# M225A.net
KiCad netlist of a schematic drawn in EAGLE
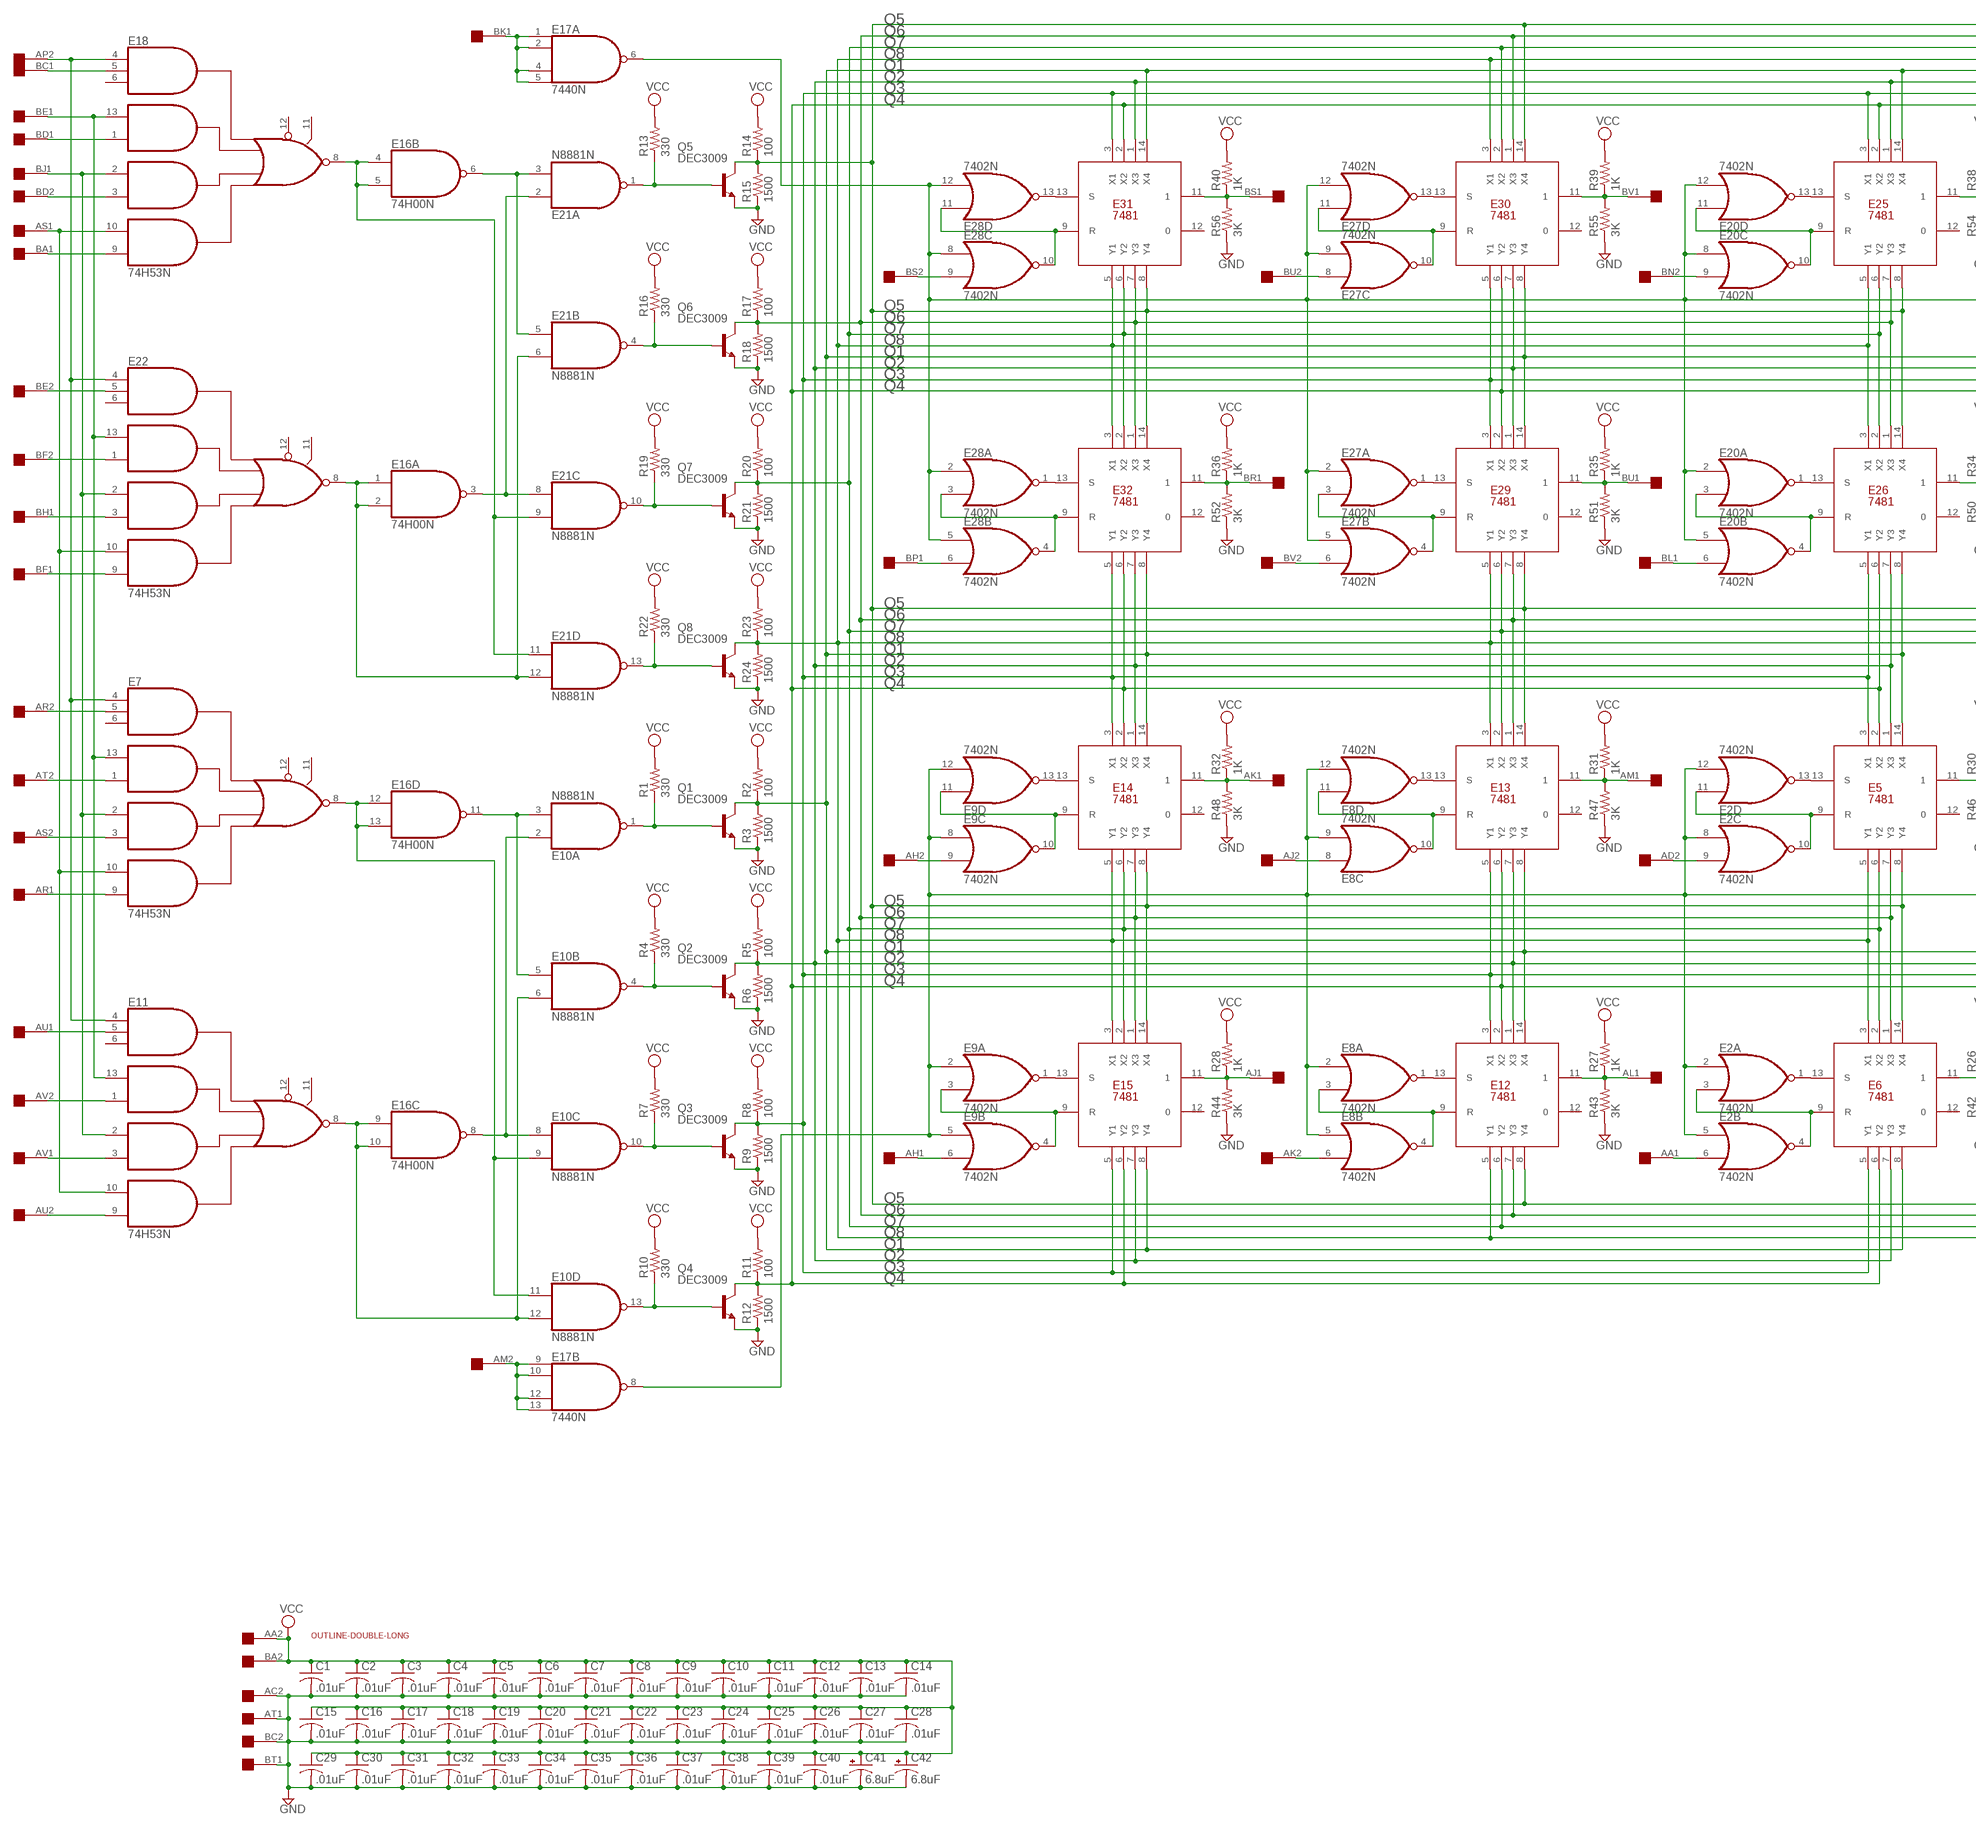
[diagram p0: schematic, sheet 1, part 1 of 2]
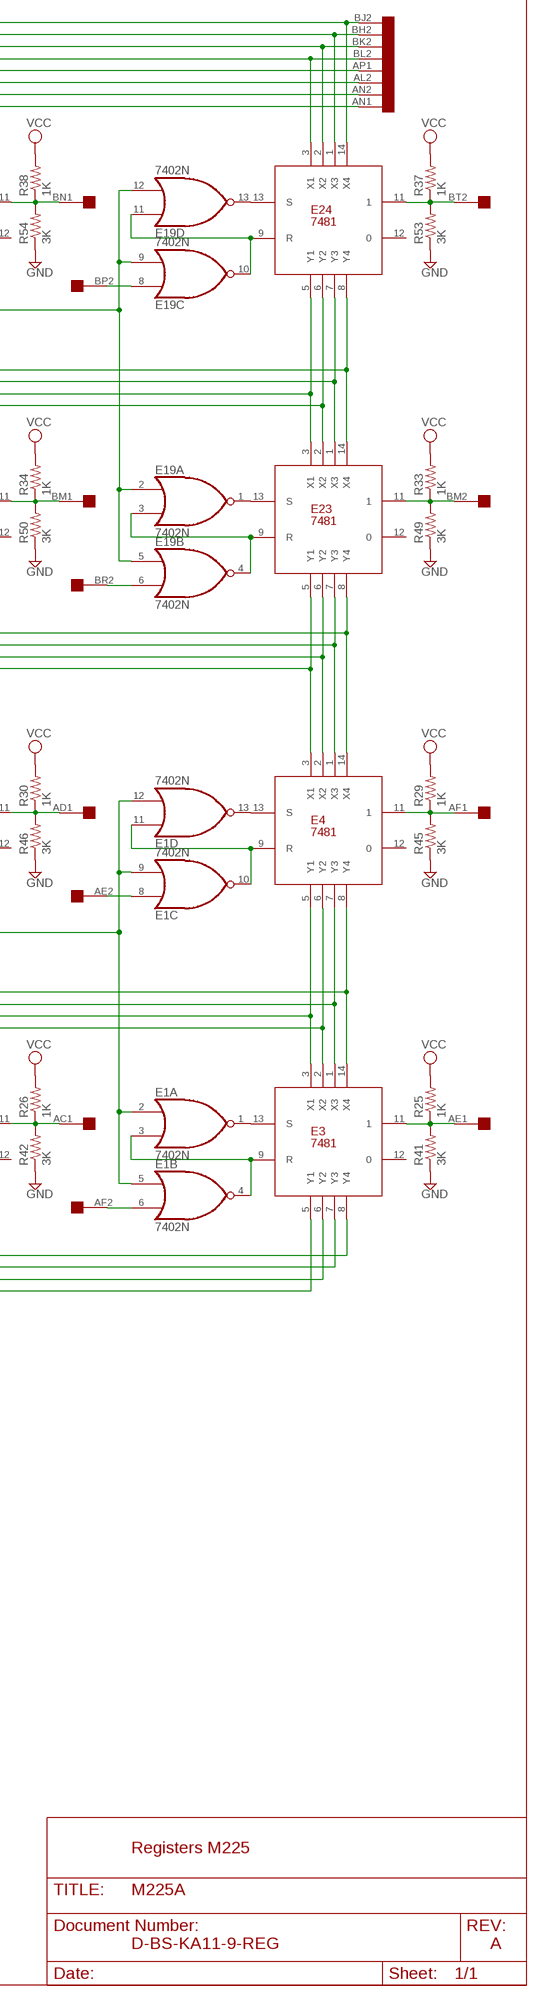
[diagram p1: schematic, sheet 1, part 2 of 2]

(export (version "E")
  (design (tool "Eeschema 10.0.6"))
  (components
    (comp (ref "C1")
      (value ".01uF")
      (footprint "eagle-import:C050-025X075")
      (libsource (lib "eagle-import") (part "C-US050-025X075"))
    )
    (comp (ref "C2")
      (value ".01uF")
      (footprint "eagle-import:C050-025X075")
      (libsource (lib "eagle-import") (part "C-US050-025X075"))
    )
    (comp (ref "C3")
      (value ".01uF")
      (footprint "eagle-import:C050-025X075")
      (libsource (lib "eagle-import") (part "C-US050-025X075"))
    )
    (comp (ref "C4")
      (value ".01uF")
      (footprint "eagle-import:C050-025X075")
      (libsource (lib "eagle-import") (part "C-US050-025X075"))
    )
    (comp (ref "C5")
      (value ".01uF")
      (footprint "eagle-import:C050-025X075")
      (libsource (lib "eagle-import") (part "C-US050-025X075"))
    )
    (comp (ref "C6")
      (value ".01uF")
      (footprint "eagle-import:C050-025X075")
      (libsource (lib "eagle-import") (part "C-US050-025X075"))
    )
    (comp (ref "C7")
      (value ".01uF")
      (footprint "eagle-import:C050-025X075")
      (libsource (lib "eagle-import") (part "C-US050-025X075"))
    )
    (comp (ref "C8")
      (value ".01uF")
      (footprint "eagle-import:C050-025X075")
      (libsource (lib "eagle-import") (part "C-US050-025X075"))
    )
    (comp (ref "C9")
      (value ".01uF")
      (footprint "eagle-import:C050-025X075")
      (libsource (lib "eagle-import") (part "C-US050-025X075"))
    )
    (comp (ref "C10")
      (value ".01uF")
      (footprint "eagle-import:C050-025X075")
      (libsource (lib "eagle-import") (part "C-US050-025X075"))
    )
    (comp (ref "C11")
      (value ".01uF")
      (footprint "eagle-import:C050-025X075")
      (libsource (lib "eagle-import") (part "C-US050-025X075"))
    )
    (comp (ref "C12")
      (value ".01uF")
      (footprint "eagle-import:C050-025X075")
      (libsource (lib "eagle-import") (part "C-US050-025X075"))
    )
    (comp (ref "C13")
      (value ".01uF")
      (footprint "eagle-import:C050-025X075")
      (libsource (lib "eagle-import") (part "C-US050-025X075"))
    )
    (comp (ref "C14")
      (value ".01uF")
      (footprint "eagle-import:C050-025X075")
      (libsource (lib "eagle-import") (part "C-US050-025X075"))
    )
    (comp (ref "C15")
      (value ".01uF")
      (footprint "eagle-import:C050-025X075")
      (libsource (lib "eagle-import") (part "C-US050-025X075"))
    )
    (comp (ref "C16")
      (value ".01uF")
      (footprint "eagle-import:C050-025X075")
      (libsource (lib "eagle-import") (part "C-US050-025X075"))
    )
    (comp (ref "C17")
      (value ".01uF")
      (footprint "eagle-import:C050-025X075")
      (libsource (lib "eagle-import") (part "C-US050-025X075"))
    )
    (comp (ref "C18")
      (value ".01uF")
      (footprint "eagle-import:C050-025X075")
      (libsource (lib "eagle-import") (part "C-US050-025X075"))
    )
    (comp (ref "C19")
      (value ".01uF")
      (footprint "eagle-import:C050-025X075")
      (libsource (lib "eagle-import") (part "C-US050-025X075"))
    )
    (comp (ref "C20")
      (value ".01uF")
      (footprint "eagle-import:C050-025X075")
      (libsource (lib "eagle-import") (part "C-US050-025X075"))
    )
    (comp (ref "C21")
      (value ".01uF")
      (footprint "eagle-import:C050-025X075")
      (libsource (lib "eagle-import") (part "C-US050-025X075"))
    )
    (comp (ref "C22")
      (value ".01uF")
      (footprint "eagle-import:C050-025X075")
      (libsource (lib "eagle-import") (part "C-US050-025X075"))
    )
    (comp (ref "C23")
      (value ".01uF")
      (footprint "eagle-import:C050-025X075")
      (libsource (lib "eagle-import") (part "C-US050-025X075"))
    )
    (comp (ref "C24")
      (value ".01uF")
      (footprint "eagle-import:C050-025X075")
      (libsource (lib "eagle-import") (part "C-US050-025X075"))
    )
    (comp (ref "C25")
      (value ".01uF")
      (footprint "eagle-import:C050-025X075")
      (libsource (lib "eagle-import") (part "C-US050-025X075"))
    )
    (comp (ref "C26")
      (value ".01uF")
      (footprint "eagle-import:C050-025X075")
      (libsource (lib "eagle-import") (part "C-US050-025X075"))
    )
    (comp (ref "C27")
      (value ".01uF")
      (footprint "eagle-import:C050-025X075")
      (libsource (lib "eagle-import") (part "C-US050-025X075"))
    )
    (comp (ref "C28")
      (value ".01uF")
      (footprint "eagle-import:C050-025X075")
      (libsource (lib "eagle-import") (part "C-US050-025X075"))
    )
    (comp (ref "C29")
      (value ".01uF")
      (footprint "eagle-import:C050-025X075")
      (libsource (lib "eagle-import") (part "C-US050-025X075"))
    )
    (comp (ref "C30")
      (value ".01uF")
      (footprint "eagle-import:C050-025X075")
      (libsource (lib "eagle-import") (part "C-US050-025X075"))
    )
    (comp (ref "C31")
      (value ".01uF")
      (footprint "eagle-import:C050-025X075")
      (libsource (lib "eagle-import") (part "C-US050-025X075"))
    )
    (comp (ref "C32")
      (value ".01uF")
      (footprint "eagle-import:C050-025X075")
      (libsource (lib "eagle-import") (part "C-US050-025X075"))
    )
    (comp (ref "C33")
      (value ".01uF")
      (footprint "eagle-import:C050-025X075")
      (libsource (lib "eagle-import") (part "C-US050-025X075"))
    )
    (comp (ref "C34")
      (value ".01uF")
      (footprint "eagle-import:C050-025X075")
      (libsource (lib "eagle-import") (part "C-US050-025X075"))
    )
    (comp (ref "C35")
      (value ".01uF")
      (footprint "eagle-import:C050-025X075")
      (libsource (lib "eagle-import") (part "C-US050-025X075"))
    )
    (comp (ref "C36")
      (value ".01uF")
      (footprint "eagle-import:C050-025X075")
      (libsource (lib "eagle-import") (part "C-US050-025X075"))
    )
    (comp (ref "C37")
      (value ".01uF")
      (footprint "eagle-import:C050-025X075")
      (libsource (lib "eagle-import") (part "C-US050-025X075"))
    )
    (comp (ref "C38")
      (value ".01uF")
      (footprint "eagle-import:C050-025X075")
      (libsource (lib "eagle-import") (part "C-US050-025X075"))
    )
    (comp (ref "C39")
      (value ".01uF")
      (footprint "eagle-import:C050-025X075")
      (libsource (lib "eagle-import") (part "C-US050-025X075"))
    )
    (comp (ref "C40")
      (value ".01uF")
      (footprint "eagle-import:C050-025X075")
      (libsource (lib "eagle-import") (part "C-US050-025X075"))
    )
    (comp (ref "C41")
      (value "6.8uF")
      (footprint "eagle-import:E12-8")
      (libsource (lib "eagle-import") (part "CPOL-USE20-8AXIAL"))
    )
    (comp (ref "C42")
      (value "6.8uF")
      (footprint "eagle-import:E12-8")
      (libsource (lib "eagle-import") (part "CPOL-USE20-8AXIAL"))
    )
    (comp (ref "E1")
      (value "7402N")
      (footprint "eagle-import:DIL14")
      (libsource (lib "eagle-import") (part "7402N"))
    )
    (comp (ref "E2")
      (value "7402N")
      (footprint "eagle-import:DIL14")
      (libsource (lib "eagle-import") (part "7402N"))
    )
    (comp (ref "E3")
      (value "7481")
      (footprint "eagle-import:DIL14")
      (libsource (lib "eagle-import") (part "7481"))
    )
    (comp (ref "E4")
      (value "7481")
      (footprint "eagle-import:DIL14")
      (libsource (lib "eagle-import") (part "7481"))
    )
    (comp (ref "E5")
      (value "7481")
      (footprint "eagle-import:DIL14")
      (libsource (lib "eagle-import") (part "7481"))
    )
    (comp (ref "E6")
      (value "7481")
      (footprint "eagle-import:DIL14")
      (libsource (lib "eagle-import") (part "7481"))
    )
    (comp (ref "E7")
      (value "74H53N")
      (footprint "eagle-import:DIL14")
      (libsource (lib "eagle-import") (part "74H53N"))
    )
    (comp (ref "E8")
      (value "7402N")
      (footprint "eagle-import:DIL14")
      (libsource (lib "eagle-import") (part "7402N"))
    )
    (comp (ref "E9")
      (value "7402N")
      (footprint "eagle-import:DIL14")
      (libsource (lib "eagle-import") (part "7402N"))
    )
    (comp (ref "E10")
      (value "N8881N")
      (footprint "eagle-import:DIL14")
      (libsource (lib "eagle-import") (part "N8881N"))
    )
    (comp (ref "E11")
      (value "74H53N")
      (footprint "eagle-import:DIL14")
      (libsource (lib "eagle-import") (part "74H53N"))
    )
    (comp (ref "E12")
      (value "7481")
      (footprint "eagle-import:DIL14")
      (libsource (lib "eagle-import") (part "7481"))
    )
    (comp (ref "E13")
      (value "7481")
      (footprint "eagle-import:DIL14")
      (libsource (lib "eagle-import") (part "7481"))
    )
    (comp (ref "E14")
      (value "7481")
      (footprint "eagle-import:DIL14")
      (libsource (lib "eagle-import") (part "7481"))
    )
    (comp (ref "E15")
      (value "7481")
      (footprint "eagle-import:DIL14")
      (libsource (lib "eagle-import") (part "7481"))
    )
    (comp (ref "E16")
      (value "74H00N")
      (footprint "eagle-import:DIL14")
      (libsource (lib "eagle-import") (part "7400NS"))
    )
    (comp (ref "E17")
      (value "7440N")
      (footprint "eagle-import:DIL14")
      (libsource (lib "eagle-import") (part "7440N"))
    )
    (comp (ref "E18")
      (value "74H53N")
      (footprint "eagle-import:DIL14")
      (libsource (lib "eagle-import") (part "74H53N"))
    )
    (comp (ref "E19")
      (value "7402N")
      (footprint "eagle-import:DIL14")
      (libsource (lib "eagle-import") (part "7402N"))
    )
    (comp (ref "E20")
      (value "7402N")
      (footprint "eagle-import:DIL14")
      (libsource (lib "eagle-import") (part "7402N"))
    )
    (comp (ref "E21")
      (value "N8881N")
      (footprint "eagle-import:DIL14")
      (libsource (lib "eagle-import") (part "N8881N"))
    )
    (comp (ref "E22")
      (value "74H53N")
      (footprint "eagle-import:DIL14")
      (libsource (lib "eagle-import") (part "74H53N"))
    )
    (comp (ref "E23")
      (value "7481")
      (footprint "eagle-import:DIL14")
      (libsource (lib "eagle-import") (part "7481"))
    )
    (comp (ref "E24")
      (value "7481")
      (footprint "eagle-import:DIL14")
      (libsource (lib "eagle-import") (part "7481"))
    )
    (comp (ref "E25")
      (value "7481")
      (footprint "eagle-import:DIL14")
      (libsource (lib "eagle-import") (part "7481"))
    )
    (comp (ref "E26")
      (value "7481")
      (footprint "eagle-import:DIL14")
      (libsource (lib "eagle-import") (part "7481"))
    )
    (comp (ref "E27")
      (value "7402N")
      (footprint "eagle-import:DIL14")
      (libsource (lib "eagle-import") (part "7402N"))
    )
    (comp (ref "E28")
      (value "7402N")
      (footprint "eagle-import:DIL14")
      (libsource (lib "eagle-import") (part "7402N"))
    )
    (comp (ref "E29")
      (value "7481")
      (footprint "eagle-import:DIL14")
      (libsource (lib "eagle-import") (part "7481"))
    )
    (comp (ref "E30")
      (value "7481")
      (footprint "eagle-import:DIL14")
      (libsource (lib "eagle-import") (part "7481"))
    )
    (comp (ref "E31")
      (value "7481")
      (footprint "eagle-import:DIL14")
      (libsource (lib "eagle-import") (part "7481"))
    )
    (comp (ref "E32")
      (value "7481")
      (footprint "eagle-import:DIL14")
      (libsource (lib "eagle-import") (part "7481"))
    )
    (comp (ref "Q1")
      (value "DEC3009")
      (footprint "eagle-import:TO5")
      (libsource (lib "eagle-import") (part "-NPN-TO5"))
    )
    (comp (ref "Q2")
      (value "DEC3009")
      (footprint "eagle-import:TO5")
      (libsource (lib "eagle-import") (part "-NPN-TO5"))
    )
    (comp (ref "Q3")
      (value "DEC3009")
      (footprint "eagle-import:TO5")
      (libsource (lib "eagle-import") (part "-NPN-TO5"))
    )
    (comp (ref "Q4")
      (value "DEC3009")
      (footprint "eagle-import:TO5")
      (libsource (lib "eagle-import") (part "-NPN-TO5"))
    )
    (comp (ref "Q5")
      (value "DEC3009")
      (footprint "eagle-import:TO5")
      (libsource (lib "eagle-import") (part "-NPN-TO5"))
    )
    (comp (ref "Q6")
      (value "DEC3009")
      (footprint "eagle-import:TO5")
      (libsource (lib "eagle-import") (part "-NPN-TO5"))
    )
    (comp (ref "Q7")
      (value "DEC3009")
      (footprint "eagle-import:TO5")
      (libsource (lib "eagle-import") (part "-NPN-TO5"))
    )
    (comp (ref "Q8")
      (value "DEC3009")
      (footprint "eagle-import:TO5")
      (libsource (lib "eagle-import") (part "-NPN-TO5"))
    )
    (comp (ref "R1")
      (value "330")
      (footprint "eagle-import:0207_10")
      (libsource (lib "eagle-import") (part "R-US_0207/10"))
    )
    (comp (ref "R2")
      (value "100")
      (footprint "eagle-import:0207_10")
      (libsource (lib "eagle-import") (part "R-US_0207/10"))
    )
    (comp (ref "R3")
      (value "1500")
      (footprint "eagle-import:0207_10")
      (libsource (lib "eagle-import") (part "R-US_0207/10"))
    )
    (comp (ref "R4")
      (value "330")
      (footprint "eagle-import:0207_10")
      (libsource (lib "eagle-import") (part "R-US_0207/10"))
    )
    (comp (ref "R5")
      (value "100")
      (footprint "eagle-import:0207_10")
      (libsource (lib "eagle-import") (part "R-US_0207/10"))
    )
    (comp (ref "R6")
      (value "1500")
      (footprint "eagle-import:0207_10")
      (libsource (lib "eagle-import") (part "R-US_0207/10"))
    )
    (comp (ref "R7")
      (value "330")
      (footprint "eagle-import:0207_10")
      (libsource (lib "eagle-import") (part "R-US_0207/10"))
    )
    (comp (ref "R8")
      (value "100")
      (footprint "eagle-import:0207_10")
      (libsource (lib "eagle-import") (part "R-US_0207/10"))
    )
    (comp (ref "R9")
      (value "1500")
      (footprint "eagle-import:0207_10")
      (libsource (lib "eagle-import") (part "R-US_0207/10"))
    )
    (comp (ref "R10")
      (value "330")
      (footprint "eagle-import:0207_10")
      (libsource (lib "eagle-import") (part "R-US_0207/10"))
    )
    (comp (ref "R11")
      (value "100")
      (footprint "eagle-import:0207_10")
      (libsource (lib "eagle-import") (part "R-US_0207/10"))
    )
    (comp (ref "R12")
      (value "1500")
      (footprint "eagle-import:0207_10")
      (libsource (lib "eagle-import") (part "R-US_0207/10"))
    )
    (comp (ref "R13")
      (value "330")
      (footprint "eagle-import:0207_10")
      (libsource (lib "eagle-import") (part "R-US_0207/10"))
    )
    (comp (ref "R14")
      (value "100")
      (footprint "eagle-import:0207_10")
      (libsource (lib "eagle-import") (part "R-US_0207/10"))
    )
    (comp (ref "R15")
      (value "1500")
      (footprint "eagle-import:0207_10")
      (libsource (lib "eagle-import") (part "R-US_0207/10"))
    )
    (comp (ref "R16")
      (value "330")
      (footprint "eagle-import:0207_10")
      (libsource (lib "eagle-import") (part "R-US_0207/10"))
    )
    (comp (ref "R17")
      (value "100")
      (footprint "eagle-import:0207_10")
      (libsource (lib "eagle-import") (part "R-US_0207/10"))
    )
    (comp (ref "R18")
      (value "1500")
      (footprint "eagle-import:0207_10")
      (libsource (lib "eagle-import") (part "R-US_0207/10"))
    )
    (comp (ref "R19")
      (value "330")
      (footprint "eagle-import:0207_10")
      (libsource (lib "eagle-import") (part "R-US_0207/10"))
    )
    (comp (ref "R20")
      (value "100")
      (footprint "eagle-import:0207_10")
      (libsource (lib "eagle-import") (part "R-US_0207/10"))
    )
    (comp (ref "R21")
      (value "1500")
      (footprint "eagle-import:0207_10")
      (libsource (lib "eagle-import") (part "R-US_0207/10"))
    )
    (comp (ref "R22")
      (value "330")
      (footprint "eagle-import:0207_10")
      (libsource (lib "eagle-import") (part "R-US_0207/10"))
    )
    (comp (ref "R23")
      (value "100")
      (footprint "eagle-import:0207_10")
      (libsource (lib "eagle-import") (part "R-US_0207/10"))
    )
    (comp (ref "R24")
      (value "1500")
      (footprint "eagle-import:0207_10")
      (libsource (lib "eagle-import") (part "R-US_0207/10"))
    )
    (comp (ref "R25")
      (value "1K")
      (footprint "eagle-import:0207_10")
      (libsource (lib "eagle-import") (part "R-US_0207/10"))
    )
    (comp (ref "R26")
      (value "1K")
      (footprint "eagle-import:0207_10")
      (libsource (lib "eagle-import") (part "R-US_0207/10"))
    )
    (comp (ref "R27")
      (value "1K")
      (footprint "eagle-import:0207_10")
      (libsource (lib "eagle-import") (part "R-US_0207/10"))
    )
    (comp (ref "R28")
      (value "1K")
      (footprint "eagle-import:0207_10")
      (libsource (lib "eagle-import") (part "R-US_0207/10"))
    )
    (comp (ref "R29")
      (value "1K")
      (footprint "eagle-import:0207_10")
      (libsource (lib "eagle-import") (part "R-US_0207/10"))
    )
    (comp (ref "R30")
      (value "1K")
      (footprint "eagle-import:0207_10")
      (libsource (lib "eagle-import") (part "R-US_0207/10"))
    )
    (comp (ref "R31")
      (value "1K")
      (footprint "eagle-import:0207_10")
      (libsource (lib "eagle-import") (part "R-US_0207/10"))
    )
    (comp (ref "R32")
      (value "1K")
      (footprint "eagle-import:0207_10")
      (libsource (lib "eagle-import") (part "R-US_0207/10"))
    )
    (comp (ref "R33")
      (value "1K")
      (footprint "eagle-import:0207_10")
      (libsource (lib "eagle-import") (part "R-US_0207/10"))
    )
    (comp (ref "R34")
      (value "1K")
      (footprint "eagle-import:0207_10")
      (libsource (lib "eagle-import") (part "R-US_0207/10"))
    )
    (comp (ref "R35")
      (value "1K")
      (footprint "eagle-import:0207_10")
      (libsource (lib "eagle-import") (part "R-US_0207/10"))
    )
    (comp (ref "R36")
      (value "1K")
      (footprint "eagle-import:0207_10")
      (libsource (lib "eagle-import") (part "R-US_0207/10"))
    )
    (comp (ref "R37")
      (value "1K")
      (footprint "eagle-import:0207_10")
      (libsource (lib "eagle-import") (part "R-US_0207/10"))
    )
    (comp (ref "R38")
      (value "1K")
      (footprint "eagle-import:0207_10")
      (libsource (lib "eagle-import") (part "R-US_0207/10"))
    )
    (comp (ref "R39")
      (value "1K")
      (footprint "eagle-import:0207_10")
      (libsource (lib "eagle-import") (part "R-US_0207/10"))
    )
    (comp (ref "R40")
      (value "1K")
      (footprint "eagle-import:0207_10")
      (libsource (lib "eagle-import") (part "R-US_0207/10"))
    )
    (comp (ref "R41")
      (value "3K")
      (footprint "eagle-import:0207_10")
      (libsource (lib "eagle-import") (part "R-US_0207/10"))
    )
    (comp (ref "R42")
      (value "3K")
      (footprint "eagle-import:0207_10")
      (libsource (lib "eagle-import") (part "R-US_0207/10"))
    )
    (comp (ref "R43")
      (value "3K")
      (footprint "eagle-import:0207_10")
      (libsource (lib "eagle-import") (part "R-US_0207/10"))
    )
    (comp (ref "R44")
      (value "3K")
      (footprint "eagle-import:0207_10")
      (libsource (lib "eagle-import") (part "R-US_0207/10"))
    )
    (comp (ref "R45")
      (value "3K")
      (footprint "eagle-import:0207_10")
      (libsource (lib "eagle-import") (part "R-US_0207/10"))
    )
    (comp (ref "R46")
      (value "3K")
      (footprint "eagle-import:0207_10")
      (libsource (lib "eagle-import") (part "R-US_0207/10"))
    )
    (comp (ref "R47")
      (value "3K")
      (footprint "eagle-import:0207_10")
      (libsource (lib "eagle-import") (part "R-US_0207/10"))
    )
    (comp (ref "R48")
      (value "3K")
      (footprint "eagle-import:0207_10")
      (libsource (lib "eagle-import") (part "R-US_0207/10"))
    )
    (comp (ref "R49")
      (value "3K")
      (footprint "eagle-import:0207_10")
      (libsource (lib "eagle-import") (part "R-US_0207/10"))
    )
    (comp (ref "R50")
      (value "3K")
      (footprint "eagle-import:0207_10")
      (libsource (lib "eagle-import") (part "R-US_0207/10"))
    )
    (comp (ref "R51")
      (value "3K")
      (footprint "eagle-import:0207_10")
      (libsource (lib "eagle-import") (part "R-US_0207/10"))
    )
    (comp (ref "R52")
      (value "3K")
      (footprint "eagle-import:0207_10")
      (libsource (lib "eagle-import") (part "R-US_0207/10"))
    )
    (comp (ref "R53")
      (value "3K")
      (footprint "eagle-import:0207_10")
      (libsource (lib "eagle-import") (part "R-US_0207/10"))
    )
    (comp (ref "R54")
      (value "3K")
      (footprint "eagle-import:0207_10")
      (libsource (lib "eagle-import") (part "R-US_0207/10"))
    )
    (comp (ref "R55")
      (value "3K")
      (footprint "eagle-import:0207_10")
      (libsource (lib "eagle-import") (part "R-US_0207/10"))
    )
    (comp (ref "R56")
      (value "3K")
      (footprint "eagle-import:0207_10")
      (libsource (lib "eagle-import") (part "R-US_0207/10"))
    )
    (comp (ref "U$1")
      (value "OUTLINE-DOUBLE-LONG")
      (footprint "eagle-import:DOUBLE-LONG")
      (libsource (lib "eagle-import") (part "OUTLINE-DOUBLE-LONG"))
    )
    (comp (ref "U$3")
      (value "DOUBLE")
      (footprint "eagle-import:EDGE-CON4")
      (libsource (lib "eagle-import") (part "DOUBLE"))
    )
  )
  (nets
    (net (code "1") (name "/Q1") (class "Default")
      (node (ref "E12") (pin "14") (pinfunction "X4_14") (pintype "input"))
      (node (ref "E13") (pin "8") (pinfunction "Y4_8") (pintype "input"))
      (node (ref "E14") (pin "14") (pinfunction "X4_14") (pintype "input"))
      (node (ref "E15") (pin "8") (pinfunction "Y4_8") (pintype "input"))
      (node (ref "E23") (pin "14") (pinfunction "X4_14") (pintype "input"))
      (node (ref "E24") (pin "8") (pinfunction "Y4_8") (pintype "input"))
      (node (ref "E25") (pin "14") (pinfunction "X4_14") (pintype "input"))
      (node (ref "E26") (pin "8") (pinfunction "Y4_8") (pintype "input"))
      (node (ref "E29") (pin "14") (pinfunction "X4_14") (pintype "input"))
      (node (ref "E3") (pin "14") (pinfunction "X4_14") (pintype "input"))
      (node (ref "E30") (pin "8") (pinfunction "Y4_8") (pintype "input"))
      (node (ref "E31") (pin "14") (pinfunction "X4_14") (pintype "input"))
      (node (ref "E32") (pin "8") (pinfunction "Y4_8") (pintype "input"))
      (node (ref "E4") (pin "8") (pinfunction "Y4_8") (pintype "input"))
      (node (ref "E5") (pin "14") (pinfunction "X4_14") (pintype "input"))
      (node (ref "E6") (pin "8") (pinfunction "Y4_8") (pintype "input"))
      (node (ref "Q1") (pin "3") (pinfunction "C_3") (pintype "passive"))
      (node (ref "R2") (pin "1") (pinfunction "1_1") (pintype "passive"))
      (node (ref "R3") (pin "2") (pinfunction "2_2") (pintype "passive"))
      (node (ref "U$3") (pin "AP1") (pinfunction "1_AP1") (pintype "bidirectional"))
    )
    (net (code "2") (name "/Q2") (class "Default")
      (node (ref "E12") (pin "1") (pinfunction "X3_1") (pintype "input"))
      (node (ref "E13") (pin "7") (pinfunction "Y3_7") (pintype "input"))
      (node (ref "E14") (pin "1") (pinfunction "X3_1") (pintype "input"))
      (node (ref "E15") (pin "7") (pinfunction "Y3_7") (pintype "input"))
      (node (ref "E23") (pin "1") (pinfunction "X3_1") (pintype "input"))
      (node (ref "E24") (pin "7") (pinfunction "Y3_7") (pintype "input"))
      (node (ref "E25") (pin "1") (pinfunction "X3_1") (pintype "input"))
      (node (ref "E26") (pin "7") (pinfunction "Y3_7") (pintype "input"))
      (node (ref "E29") (pin "1") (pinfunction "X3_1") (pintype "input"))
      (node (ref "E3") (pin "1") (pinfunction "X3_1") (pintype "input"))
      (node (ref "E30") (pin "7") (pinfunction "Y3_7") (pintype "input"))
      (node (ref "E31") (pin "1") (pinfunction "X3_1") (pintype "input"))
      (node (ref "E32") (pin "7") (pinfunction "Y3_7") (pintype "input"))
      (node (ref "E4") (pin "7") (pinfunction "Y3_7") (pintype "input"))
      (node (ref "E5") (pin "1") (pinfunction "X3_1") (pintype "input"))
      (node (ref "E6") (pin "7") (pinfunction "Y3_7") (pintype "input"))
      (node (ref "Q2") (pin "3") (pinfunction "C_3") (pintype "passive"))
      (node (ref "R5") (pin "1") (pinfunction "1_1") (pintype "passive"))
      (node (ref "R6") (pin "2") (pinfunction "2_2") (pintype "passive"))
      (node (ref "U$3") (pin "AL2") (pinfunction "1_AL2") (pintype "bidirectional"))
    )
    (net (code "3") (name "/Q3") (class "Default")
      (node (ref "E12") (pin "3") (pinfunction "X1_3") (pintype "input"))
      (node (ref "E13") (pin "5") (pinfunction "Y1_5") (pintype "input"))
      (node (ref "E14") (pin "3") (pinfunction "X1_3") (pintype "input"))
      (node (ref "E15") (pin "5") (pinfunction "Y1_5") (pintype "input"))
      (node (ref "E23") (pin "3") (pinfunction "X1_3") (pintype "input"))
      (node (ref "E24") (pin "5") (pinfunction "Y1_5") (pintype "input"))
      (node (ref "E25") (pin "3") (pinfunction "X1_3") (pintype "input"))
      (node (ref "E26") (pin "5") (pinfunction "Y1_5") (pintype "input"))
      (node (ref "E29") (pin "3") (pinfunction "X1_3") (pintype "input"))
      (node (ref "E3") (pin "3") (pinfunction "X1_3") (pintype "input"))
      (node (ref "E30") (pin "5") (pinfunction "Y1_5") (pintype "input"))
      (node (ref "E31") (pin "3") (pinfunction "X1_3") (pintype "input"))
      (node (ref "E32") (pin "5") (pinfunction "Y1_5") (pintype "input"))
      (node (ref "E4") (pin "5") (pinfunction "Y1_5") (pintype "input"))
      (node (ref "E5") (pin "3") (pinfunction "X1_3") (pintype "input"))
      (node (ref "E6") (pin "5") (pinfunction "Y1_5") (pintype "input"))
      (node (ref "Q3") (pin "3") (pinfunction "C_3") (pintype "passive"))
      (node (ref "R8") (pin "1") (pinfunction "1_1") (pintype "passive"))
      (node (ref "R9") (pin "2") (pinfunction "2_2") (pintype "passive"))
      (node (ref "U$3") (pin "AN2") (pinfunction "1_AN2") (pintype "bidirectional"))
    )
    (net (code "4") (name "/Q4") (class "Default")
      (node (ref "E12") (pin "2") (pinfunction "X2_2") (pintype "input"))
      (node (ref "E13") (pin "6") (pinfunction "Y2_6") (pintype "input"))
      (node (ref "E14") (pin "2") (pinfunction "X2_2") (pintype "input"))
      (node (ref "E15") (pin "6") (pinfunction "Y2_6") (pintype "input"))
      (node (ref "E23") (pin "2") (pinfunction "X2_2") (pintype "input"))
      (node (ref "E24") (pin "6") (pinfunction "Y2_6") (pintype "input"))
      (node (ref "E25") (pin "2") (pinfunction "X2_2") (pintype "input"))
      (node (ref "E26") (pin "6") (pinfunction "Y2_6") (pintype "input"))
      (node (ref "E29") (pin "2") (pinfunction "X2_2") (pintype "input"))
      (node (ref "E3") (pin "2") (pinfunction "X2_2") (pintype "input"))
      (node (ref "E30") (pin "6") (pinfunction "Y2_6") (pintype "input"))
      (node (ref "E31") (pin "2") (pinfunction "X2_2") (pintype "input"))
      (node (ref "E32") (pin "6") (pinfunction "Y2_6") (pintype "input"))
      (node (ref "E4") (pin "6") (pinfunction "Y2_6") (pintype "input"))
      (node (ref "E5") (pin "2") (pinfunction "X2_2") (pintype "input"))
      (node (ref "E6") (pin "6") (pinfunction "Y2_6") (pintype "input"))
      (node (ref "Q4") (pin "3") (pinfunction "C_3") (pintype "passive"))
      (node (ref "R11") (pin "1") (pinfunction "1_1") (pintype "passive"))
      (node (ref "R12") (pin "2") (pinfunction "2_2") (pintype "passive"))
      (node (ref "U$3") (pin "AN1") (pinfunction "1_AN1") (pintype "bidirectional"))
    )
    (net (code "5") (name "/Q5") (class "Default")
      (node (ref "E12") (pin "8") (pinfunction "Y4_8") (pintype "input"))
      (node (ref "E13") (pin "14") (pinfunction "X4_14") (pintype "input"))
      (node (ref "E14") (pin "8") (pinfunction "Y4_8") (pintype "input"))
      (node (ref "E15") (pin "14") (pinfunction "X4_14") (pintype "input"))
      (node (ref "E23") (pin "8") (pinfunction "Y4_8") (pintype "input"))
      (node (ref "E24") (pin "14") (pinfunction "X4_14") (pintype "input"))
      (node (ref "E25") (pin "8") (pinfunction "Y4_8") (pintype "input"))
      (node (ref "E26") (pin "14") (pinfunction "X4_14") (pintype "input"))
      (node (ref "E29") (pin "8") (pinfunction "Y4_8") (pintype "input"))
      (node (ref "E3") (pin "8") (pinfunction "Y4_8") (pintype "input"))
      (node (ref "E30") (pin "14") (pinfunction "X4_14") (pintype "input"))
      (node (ref "E31") (pin "8") (pinfunction "Y4_8") (pintype "input"))
      (node (ref "E32") (pin "14") (pinfunction "X4_14") (pintype "input"))
      (node (ref "E4") (pin "14") (pinfunction "X4_14") (pintype "input"))
      (node (ref "E5") (pin "8") (pinfunction "Y4_8") (pintype "input"))
      (node (ref "E6") (pin "14") (pinfunction "X4_14") (pintype "input"))
      (node (ref "Q5") (pin "3") (pinfunction "C_3") (pintype "passive"))
      (node (ref "R14") (pin "1") (pinfunction "1_1") (pintype "passive"))
      (node (ref "R15") (pin "2") (pinfunction "2_2") (pintype "passive"))
      (node (ref "U$3") (pin "BJ2") (pinfunction "1_BJ2") (pintype "bidirectional"))
    )
    (net (code "6") (name "/Q6") (class "Default")
      (node (ref "E12") (pin "7") (pinfunction "Y3_7") (pintype "input"))
      (node (ref "E13") (pin "1") (pinfunction "X3_1") (pintype "input"))
      (node (ref "E14") (pin "7") (pinfunction "Y3_7") (pintype "input"))
      (node (ref "E15") (pin "1") (pinfunction "X3_1") (pintype "input"))
      (node (ref "E23") (pin "7") (pinfunction "Y3_7") (pintype "input"))
      (node (ref "E24") (pin "1") (pinfunction "X3_1") (pintype "input"))
      (node (ref "E25") (pin "7") (pinfunction "Y3_7") (pintype "input"))
      (node (ref "E26") (pin "1") (pinfunction "X3_1") (pintype "input"))
      (node (ref "E29") (pin "7") (pinfunction "Y3_7") (pintype "input"))
      (node (ref "E3") (pin "7") (pinfunction "Y3_7") (pintype "input"))
      (node (ref "E30") (pin "1") (pinfunction "X3_1") (pintype "input"))
      (node (ref "E31") (pin "7") (pinfunction "Y3_7") (pintype "input"))
      (node (ref "E32") (pin "1") (pinfunction "X3_1") (pintype "input"))
      (node (ref "E4") (pin "1") (pinfunction "X3_1") (pintype "input"))
      (node (ref "E5") (pin "7") (pinfunction "Y3_7") (pintype "input"))
      (node (ref "E6") (pin "1") (pinfunction "X3_1") (pintype "input"))
      (node (ref "Q6") (pin "3") (pinfunction "C_3") (pintype "passive"))
      (node (ref "R17") (pin "1") (pinfunction "1_1") (pintype "passive"))
      (node (ref "R18") (pin "2") (pinfunction "2_2") (pintype "passive"))
      (node (ref "U$3") (pin "BH2") (pinfunction "1_BH2") (pintype "bidirectional"))
    )
    (net (code "7") (name "/Q7") (class "Default")
      (node (ref "E12") (pin "6") (pinfunction "Y2_6") (pintype "input"))
      (node (ref "E13") (pin "2") (pinfunction "X2_2") (pintype "input"))
      (node (ref "E14") (pin "6") (pinfunction "Y2_6") (pintype "input"))
      (node (ref "E15") (pin "2") (pinfunction "X2_2") (pintype "input"))
      (node (ref "E23") (pin "6") (pinfunction "Y2_6") (pintype "input"))
      (node (ref "E24") (pin "2") (pinfunction "X2_2") (pintype "input"))
      (node (ref "E25") (pin "6") (pinfunction "Y2_6") (pintype "input"))
      (node (ref "E26") (pin "2") (pinfunction "X2_2") (pintype "input"))
      (node (ref "E29") (pin "6") (pinfunction "Y2_6") (pintype "input"))
      (node (ref "E3") (pin "6") (pinfunction "Y2_6") (pintype "input"))
      (node (ref "E30") (pin "2") (pinfunction "X2_2") (pintype "input"))
      (node (ref "E31") (pin "6") (pinfunction "Y2_6") (pintype "input"))
      (node (ref "E32") (pin "2") (pinfunction "X2_2") (pintype "input"))
      (node (ref "E4") (pin "2") (pinfunction "X2_2") (pintype "input"))
      (node (ref "E5") (pin "6") (pinfunction "Y2_6") (pintype "input"))
      (node (ref "E6") (pin "2") (pinfunction "X2_2") (pintype "input"))
      (node (ref "Q7") (pin "3") (pinfunction "C_3") (pintype "passive"))
      (node (ref "R20") (pin "1") (pinfunction "1_1") (pintype "passive"))
      (node (ref "R21") (pin "2") (pinfunction "2_2") (pintype "passive"))
      (node (ref "U$3") (pin "BK2") (pinfunction "1_BK2") (pintype "bidirectional"))
    )
    (net (code "8") (name "/Q8") (class "Default")
      (node (ref "E12") (pin "5") (pinfunction "Y1_5") (pintype "input"))
      (node (ref "E13") (pin "3") (pinfunction "X1_3") (pintype "input"))
      (node (ref "E14") (pin "5") (pinfunction "Y1_5") (pintype "input"))
      (node (ref "E15") (pin "3") (pinfunction "X1_3") (pintype "input"))
      (node (ref "E23") (pin "5") (pinfunction "Y1_5") (pintype "input"))
      (node (ref "E24") (pin "3") (pinfunction "X1_3") (pintype "input"))
      (node (ref "E25") (pin "5") (pinfunction "Y1_5") (pintype "input"))
      (node (ref "E26") (pin "3") (pinfunction "X1_3") (pintype "input"))
      (node (ref "E29") (pin "5") (pinfunction "Y1_5") (pintype "input"))
      (node (ref "E3") (pin "5") (pinfunction "Y1_5") (pintype "input"))
      (node (ref "E30") (pin "3") (pinfunction "X1_3") (pintype "input"))
      (node (ref "E31") (pin "5") (pinfunction "Y1_5") (pintype "input"))
      (node (ref "E32") (pin "3") (pinfunction "X1_3") (pintype "input"))
      (node (ref "E4") (pin "3") (pinfunction "X1_3") (pintype "input"))
      (node (ref "E5") (pin "5") (pinfunction "Y1_5") (pintype "input"))
      (node (ref "E6") (pin "3") (pinfunction "X1_3") (pintype "input"))
      (node (ref "Q8") (pin "3") (pinfunction "C_3") (pintype "passive"))
      (node (ref "R23") (pin "1") (pinfunction "1_1") (pintype "passive"))
      (node (ref "R24") (pin "2") (pinfunction "2_2") (pintype "passive"))
      (node (ref "U$3") (pin "BL2") (pinfunction "1_BL2") (pintype "bidirectional"))
    )
    (net (code "9") (name "GND") (class "Default")
      (node (ref "C1") (pin "2") (pinfunction "2_2") (pintype "passive"))
      (node (ref "C10") (pin "2") (pinfunction "2_2") (pintype "passive"))
      (node (ref "C11") (pin "2") (pinfunction "2_2") (pintype "passive"))
      (node (ref "C12") (pin "2") (pinfunction "2_2") (pintype "passive"))
      (node (ref "C13") (pin "2") (pinfunction "2_2") (pintype "passive"))
      (node (ref "C14") (pin "2") (pinfunction "2_2") (pintype "passive"))
      (node (ref "C15") (pin "2") (pinfunction "2_2") (pintype "passive"))
      (node (ref "C16") (pin "2") (pinfunction "2_2") (pintype "passive"))
      (node (ref "C17") (pin "2") (pinfunction "2_2") (pintype "passive"))
      (node (ref "C18") (pin "2") (pinfunction "2_2") (pintype "passive"))
      (node (ref "C19") (pin "2") (pinfunction "2_2") (pintype "passive"))
      (node (ref "C2") (pin "2") (pinfunction "2_2") (pintype "passive"))
      (node (ref "C20") (pin "2") (pinfunction "2_2") (pintype "passive"))
      (node (ref "C21") (pin "2") (pinfunction "2_2") (pintype "passive"))
      (node (ref "C22") (pin "2") (pinfunction "2_2") (pintype "passive"))
      (node (ref "C23") (pin "2") (pinfunction "2_2") (pintype "passive"))
      (node (ref "C24") (pin "2") (pinfunction "2_2") (pintype "passive"))
      (node (ref "C25") (pin "2") (pinfunction "2_2") (pintype "passive"))
      (node (ref "C26") (pin "2") (pinfunction "2_2") (pintype "passive"))
      (node (ref "C27") (pin "2") (pinfunction "2_2") (pintype "passive"))
      (node (ref "C28") (pin "2") (pinfunction "2_2") (pintype "passive"))
      (node (ref "C29") (pin "2") (pinfunction "2_2") (pintype "passive"))
      (node (ref "C3") (pin "2") (pinfunction "2_2") (pintype "passive"))
      (node (ref "C30") (pin "2") (pinfunction "2_2") (pintype "passive"))
      (node (ref "C31") (pin "2") (pinfunction "2_2") (pintype "passive"))
      (node (ref "C32") (pin "2") (pinfunction "2_2") (pintype "passive"))
      (node (ref "C33") (pin "2") (pinfunction "2_2") (pintype "passive"))
      (node (ref "C34") (pin "2") (pinfunction "2_2") (pintype "passive"))
      (node (ref "C35") (pin "2") (pinfunction "2_2") (pintype "passive"))
      (node (ref "C36") (pin "2") (pinfunction "2_2") (pintype "passive"))
      (node (ref "C37") (pin "2") (pinfunction "2_2") (pintype "passive"))
      (node (ref "C38") (pin "2") (pinfunction "2_2") (pintype "passive"))
      (node (ref "C39") (pin "2") (pinfunction "2_2") (pintype "passive"))
      (node (ref "C4") (pin "2") (pinfunction "2_2") (pintype "passive"))
      (node (ref "C40") (pin "2") (pinfunction "2_2") (pintype "passive"))
      (node (ref "C41") (pin "-") (pinfunction "-_-") (pintype "passive"))
      (node (ref "C42") (pin "-") (pinfunction "-_-") (pintype "passive"))
      (node (ref "C5") (pin "2") (pinfunction "2_2") (pintype "passive"))
      (node (ref "C6") (pin "2") (pinfunction "2_2") (pintype "passive"))
      (node (ref "C7") (pin "2") (pinfunction "2_2") (pintype "passive"))
      (node (ref "C8") (pin "2") (pinfunction "2_2") (pintype "passive"))
      (node (ref "C9") (pin "2") (pinfunction "2_2") (pintype "passive"))
      (node (ref "Q1") (pin "1") (pinfunction "E_1") (pintype "passive"))
      (node (ref "Q2") (pin "1") (pinfunction "E_1") (pintype "passive"))
      (node (ref "Q3") (pin "1") (pinfunction "E_1") (pintype "passive"))
      (node (ref "Q4") (pin "1") (pinfunction "E_1") (pintype "passive"))
      (node (ref "Q5") (pin "1") (pinfunction "E_1") (pintype "passive"))
      (node (ref "Q6") (pin "1") (pinfunction "E_1") (pintype "passive"))
      (node (ref "Q7") (pin "1") (pinfunction "E_1") (pintype "passive"))
      (node (ref "Q8") (pin "1") (pinfunction "E_1") (pintype "passive"))
      (node (ref "R12") (pin "1") (pinfunction "1_1") (pintype "passive"))
      (node (ref "R15") (pin "1") (pinfunction "1_1") (pintype "passive"))
      (node (ref "R18") (pin "1") (pinfunction "1_1") (pintype "passive"))
      (node (ref "R21") (pin "1") (pinfunction "1_1") (pintype "passive"))
      (node (ref "R24") (pin "1") (pinfunction "1_1") (pintype "passive"))
      (node (ref "R3") (pin "1") (pinfunction "1_1") (pintype "passive"))
      (node (ref "R41") (pin "1") (pinfunction "1_1") (pintype "passive"))
      (node (ref "R42") (pin "1") (pinfunction "1_1") (pintype "passive"))
      (node (ref "R43") (pin "1") (pinfunction "1_1") (pintype "passive"))
      (node (ref "R44") (pin "1") (pinfunction "1_1") (pintype "passive"))
      (node (ref "R45") (pin "1") (pinfunction "1_1") (pintype "passive"))
      (node (ref "R46") (pin "1") (pinfunction "1_1") (pintype "passive"))
      (node (ref "R47") (pin "1") (pinfunction "1_1") (pintype "passive"))
      (node (ref "R48") (pin "1") (pinfunction "1_1") (pintype "passive"))
      (node (ref "R49") (pin "1") (pinfunction "1_1") (pintype "passive"))
      (node (ref "R50") (pin "1") (pinfunction "1_1") (pintype "passive"))
      (node (ref "R51") (pin "1") (pinfunction "1_1") (pintype "passive"))
      (node (ref "R52") (pin "1") (pinfunction "1_1") (pintype "passive"))
      (node (ref "R53") (pin "1") (pinfunction "1_1") (pintype "passive"))
      (node (ref "R54") (pin "1") (pinfunction "1_1") (pintype "passive"))
      (node (ref "R55") (pin "1") (pinfunction "1_1") (pintype "passive"))
      (node (ref "R56") (pin "1") (pinfunction "1_1") (pintype "passive"))
      (node (ref "R6") (pin "1") (pinfunction "1_1") (pintype "passive"))
      (node (ref "R9") (pin "1") (pinfunction "1_1") (pintype "passive"))
      (node (ref "U$3") (pin "AC2") (pinfunction "1_AC2") (pintype "bidirectional"))
      (node (ref "U$3") (pin "AT1") (pinfunction "1_AT1") (pintype "bidirectional"))
      (node (ref "U$3") (pin "BC2") (pinfunction "1_BC2") (pintype "bidirectional"))
      (node (ref "U$3") (pin "BT1") (pinfunction "1_BT1") (pintype "bidirectional"))
    )
    (net (code "10") (name "Net-(E1A-I1)") (class "Default")
      (node (ref "E1") (pin "3") (pinfunction "I1_3") (pintype "input"))
      (node (ref "E1") (pin "4") (pinfunction "O_4") (pintype "output"))
      (node (ref "E3") (pin "9") (pinfunction "R_9") (pintype "input"))
    )
    (net (code "11") (name "Net-(E1A-O)") (class "Default")
      (node (ref "E1") (pin "1") (pinfunction "O_1") (pintype "output"))
      (node (ref "E3") (pin "13") (pinfunction "S_13") (pintype "input"))
    )
    (net (code "12") (name "Net-(E1B-I1)") (class "Default")
      (node (ref "E1") (pin "6") (pinfunction "I1_6") (pintype "input"))
      (node (ref "U$3") (pin "AF2") (pinfunction "1_AF2") (pintype "bidirectional"))
    )
    (net (code "13") (name "Net-(E1C-I0)") (class "Default")
      (node (ref "E1") (pin "8") (pinfunction "I0_8") (pintype "input"))
      (node (ref "U$3") (pin "AE2") (pinfunction "1_AE2") (pintype "bidirectional"))
    )
    (net (code "14") (name "Net-(E1C-O)") (class "Default")
      (node (ref "E1") (pin "10") (pinfunction "O_10") (pintype "output"))
      (node (ref "E1") (pin "11") (pinfunction "I0_11") (pintype "input"))
      (node (ref "E4") (pin "9") (pinfunction "R_9") (pintype "input"))
    )
    (net (code "15") (name "Net-(E1D-O)") (class "Default")
      (node (ref "E1") (pin "13") (pinfunction "O_13") (pintype "output"))
      (node (ref "E4") (pin "13") (pinfunction "S_13") (pintype "input"))
    )
    (net (code "16") (name "Net-(E2A-I1)") (class "Default")
      (node (ref "E2") (pin "3") (pinfunction "I1_3") (pintype "input"))
      (node (ref "E2") (pin "4") (pinfunction "O_4") (pintype "output"))
      (node (ref "E6") (pin "9") (pinfunction "R_9") (pintype "input"))
    )
    (net (code "17") (name "Net-(E2A-O)") (class "Default")
      (node (ref "E2") (pin "1") (pinfunction "O_1") (pintype "output"))
      (node (ref "E6") (pin "13") (pinfunction "S_13") (pintype "input"))
    )
    (net (code "18") (name "Net-(E2B-I1)") (class "Default")
      (node (ref "E2") (pin "6") (pinfunction "I1_6") (pintype "input"))
      (node (ref "U$3") (pin "AA1") (pinfunction "1_AA1") (pintype "bidirectional"))
    )
    (net (code "19") (name "Net-(E2C-I1)") (class "Default")
      (node (ref "E2") (pin "9") (pinfunction "I1_9") (pintype "input"))
      (node (ref "U$3") (pin "AD2") (pinfunction "1_AD2") (pintype "bidirectional"))
    )
    (net (code "20") (name "Net-(E2C-O)") (class "Default")
      (node (ref "E2") (pin "10") (pinfunction "O_10") (pintype "output"))
      (node (ref "E2") (pin "11") (pinfunction "I0_11") (pintype "input"))
      (node (ref "E5") (pin "9") (pinfunction "R_9") (pintype "input"))
    )
    (net (code "21") (name "Net-(E2D-O)") (class "Default")
      (node (ref "E2") (pin "13") (pinfunction "O_13") (pintype "output"))
      (node (ref "E5") (pin "13") (pinfunction "S_13") (pintype "input"))
    )
    (net (code "22") (name "Net-(E3A-1)") (class "Default")
      (node (ref "E3") (pin "11") (pinfunction "1_11") (pintype "output"))
      (node (ref "R25") (pin "1") (pinfunction "1_1") (pintype "passive"))
      (node (ref "R41") (pin "2") (pinfunction "2_2") (pintype "passive"))
      (node (ref "U$3") (pin "AE1") (pinfunction "1_AE1") (pintype "bidirectional"))
    )
    (net (code "23") (name "Net-(E4A-1)") (class "Default")
      (node (ref "E4") (pin "11") (pinfunction "1_11") (pintype "output"))
      (node (ref "R29") (pin "1") (pinfunction "1_1") (pintype "passive"))
      (node (ref "R45") (pin "2") (pinfunction "2_2") (pintype "passive"))
      (node (ref "U$3") (pin "AF1") (pinfunction "1_AF1") (pintype "bidirectional"))
    )
    (net (code "24") (name "Net-(E5A-1)") (class "Default")
      (node (ref "E5") (pin "11") (pinfunction "1_11") (pintype "output"))
      (node (ref "R30") (pin "1") (pinfunction "1_1") (pintype "passive"))
      (node (ref "R46") (pin "2") (pinfunction "2_2") (pintype "passive"))
      (node (ref "U$3") (pin "AD1") (pinfunction "1_AD1") (pintype "bidirectional"))
    )
    (net (code "25") (name "Net-(E6A-1)") (class "Default")
      (node (ref "E6") (pin "11") (pinfunction "1_11") (pintype "output"))
      (node (ref "R26") (pin "1") (pinfunction "1_1") (pintype "passive"))
      (node (ref "R42") (pin "2") (pinfunction "2_2") (pintype "passive"))
      (node (ref "U$3") (pin "AC1") (pinfunction "1_AC1") (pintype "bidirectional"))
    )
    (net (code "26") (name "Net-(E7A-I4)") (class "Default")
      (node (ref "E7") (pin "1") (pinfunction "I4_1") (pintype "input"))
      (node (ref "U$3") (pin "AT2") (pinfunction "1_AT2") (pintype "bidirectional"))
    )
    (net (code "27") (name "Net-(E7A-I6)") (class "Default")
      (node (ref "E7") (pin "3") (pinfunction "I6_3") (pintype "input"))
      (node (ref "U$3") (pin "AS2") (pinfunction "1_AS2") (pintype "bidirectional"))
    )
    (net (code "28") (name "Net-(E7A-I8)") (class "Default")
      (node (ref "E7") (pin "9") (pinfunction "I8_9") (pintype "input"))
      (node (ref "U$3") (pin "AR1") (pinfunction "1_AR1") (pintype "bidirectional"))
    )
    (net (code "29") (name "Net-(E7A-I11)") (class "Default")
      (node (ref "E7") (pin "5") (pinfunction "I11_5") (pintype "input"))
      (node (ref "U$3") (pin "AR2") (pinfunction "1_AR2") (pintype "bidirectional"))
    )
    (net (code "30") (name "Net-(E8B-I1)") (class "Default")
      (node (ref "E8") (pin "6") (pinfunction "I1_6") (pintype "input"))
      (node (ref "U$3") (pin "AK2") (pinfunction "1_AK2") (pintype "bidirectional"))
    )
    (net (code "31") (name "Net-(E8C-I0)") (class "Default")
      (node (ref "E8") (pin "8") (pinfunction "I0_8") (pintype "input"))
      (node (ref "U$3") (pin "AJ2") (pinfunction "1_AJ2") (pintype "bidirectional"))
    )
    (net (code "32") (name "Net-(E9B-I1)") (class "Default")
      (node (ref "E9") (pin "6") (pinfunction "I1_6") (pintype "input"))
      (node (ref "U$3") (pin "AH1") (pinfunction "1_AH1") (pintype "bidirectional"))
    )
    (net (code "33") (name "Net-(E9C-I1)") (class "Default")
      (node (ref "E9") (pin "9") (pinfunction "I1_9") (pintype "input"))
      (node (ref "U$3") (pin "AH2") (pinfunction "1_AH2") (pintype "bidirectional"))
    )
    (net (code "34") (name "Net-(E10A-I0)") (class "Default")
      (node (ref "E10") (pin "2") (pinfunction "I0_2") (pintype "input"))
      (node (ref "E10") (pin "8") (pinfunction "I0_8") (pintype "input"))
      (node (ref "E16") (pin "8") (pinfunction "O_8") (pintype "output"))
    )
    (net (code "35") (name "Net-(E10A-I1)") (class "Default")
      (node (ref "E10") (pin "3") (pinfunction "I1_3") (pintype "input"))
      (node (ref "E10") (pin "5") (pinfunction "I0_5") (pintype "input"))
      (node (ref "E16") (pin "11") (pinfunction "O_11") (pintype "output"))
    )
    (net (code "36") (name "Net-(E10A-O)") (class "Default")
      (node (ref "E10") (pin "1") (pinfunction "O_1") (pintype "open_collector"))
      (node (ref "Q1") (pin "2") (pinfunction "B_2") (pintype "passive"))
      (node (ref "R1") (pin "1") (pinfunction "1_1") (pintype "passive"))
    )
    (net (code "37") (name "Net-(E10B-I1)") (class "Default")
      (node (ref "E10") (pin "12") (pinfunction "I1_12") (pintype "input"))
      (node (ref "E10") (pin "6") (pinfunction "I1_6") (pintype "input"))
      (node (ref "E11") (pin "8") (pinfunction "O_8") (pintype "output"))
      (node (ref "E16") (pin "10") (pinfunction "I1_10") (pintype "input"))
      (node (ref "E16") (pin "9") (pinfunction "I0_9") (pintype "input"))
    )
    (net (code "38") (name "Net-(E10B-O)") (class "Default")
      (node (ref "E10") (pin "4") (pinfunction "O_4") (pintype "open_collector"))
      (node (ref "Q2") (pin "2") (pinfunction "B_2") (pintype "passive"))
      (node (ref "R4") (pin "1") (pinfunction "1_1") (pintype "passive"))
    )
    (net (code "39") (name "Net-(E10C-I1)") (class "Default")
      (node (ref "E10") (pin "11") (pinfunction "I0_11") (pintype "input"))
      (node (ref "E10") (pin "9") (pinfunction "I1_9") (pintype "input"))
      (node (ref "E16") (pin "12") (pinfunction "I0_12") (pintype "input"))
      (node (ref "E16") (pin "13") (pinfunction "I1_13") (pintype "input"))
      (node (ref "E7") (pin "8") (pinfunction "O_8") (pintype "output"))
    )
    (net (code "40") (name "Net-(E10C-O)") (class "Default")
      (node (ref "E10") (pin "10") (pinfunction "O_10") (pintype "open_collector"))
      (node (ref "Q3") (pin "2") (pinfunction "B_2") (pintype "passive"))
      (node (ref "R7") (pin "1") (pinfunction "1_1") (pintype "passive"))
    )
    (net (code "41") (name "Net-(E10D-O)") (class "Default")
      (node (ref "E10") (pin "13") (pinfunction "O_13") (pintype "open_collector"))
      (node (ref "Q4") (pin "2") (pinfunction "B_2") (pintype "passive"))
      (node (ref "R10") (pin "1") (pinfunction "1_1") (pintype "passive"))
    )
    (net (code "42") (name "Net-(E11A-I1)") (class "Default")
      (node (ref "E11") (pin "4") (pinfunction "I1_4") (pintype "input"))
      (node (ref "E18") (pin "4") (pinfunction "I1_4") (pintype "input"))
      (node (ref "E22") (pin "4") (pinfunction "I1_4") (pintype "input"))
      (node (ref "E7") (pin "4") (pinfunction "I1_4") (pintype "input"))
      (node (ref "U$3") (pin "AP2") (pinfunction "1_AP2") (pintype "bidirectional"))
    )
    (net (code "43") (name "Net-(E11A-I3)") (class "Default")
      (node (ref "E11") (pin "13") (pinfunction "I3_13") (pintype "input"))
      (node (ref "E18") (pin "13") (pinfunction "I3_13") (pintype "input"))
      (node (ref "E22") (pin "13") (pinfunction "I3_13") (pintype "input"))
      (node (ref "E7") (pin "13") (pinfunction "I3_13") (pintype "input"))
      (node (ref "U$3") (pin "BE1") (pinfunction "1_BE1") (pintype "bidirectional"))
    )
    (net (code "44") (name "Net-(E11A-I4)") (class "Default")
      (node (ref "E11") (pin "1") (pinfunction "I4_1") (pintype "input"))
      (node (ref "U$3") (pin "AV2") (pinfunction "1_AV2") (pintype "bidirectional"))
    )
    (net (code "45") (name "Net-(E11A-I5)") (class "Default")
      (node (ref "E11") (pin "2") (pinfunction "I5_2") (pintype "input"))
      (node (ref "E18") (pin "2") (pinfunction "I5_2") (pintype "input"))
      (node (ref "E22") (pin "2") (pinfunction "I5_2") (pintype "input"))
      (node (ref "E7") (pin "2") (pinfunction "I5_2") (pintype "input"))
      (node (ref "U$3") (pin "BJ1") (pinfunction "1_BJ1") (pintype "bidirectional"))
    )
    (net (code "46") (name "Net-(E11A-I6)") (class "Default")
      (node (ref "E11") (pin "3") (pinfunction "I6_3") (pintype "input"))
      (node (ref "U$3") (pin "AV1") (pinfunction "1_AV1") (pintype "bidirectional"))
    )
    (net (code "47") (name "Net-(E11A-I7)") (class "Default")
      (node (ref "E11") (pin "10") (pinfunction "I7_10") (pintype "input"))
      (node (ref "E18") (pin "10") (pinfunction "I7_10") (pintype "input"))
      (node (ref "E22") (pin "10") (pinfunction "I7_10") (pintype "input"))
      (node (ref "E7") (pin "10") (pinfunction "I7_10") (pintype "input"))
      (node (ref "U$3") (pin "AS1") (pinfunction "1_AS1") (pintype "bidirectional"))
    )
    (net (code "48") (name "Net-(E11A-I8)") (class "Default")
      (node (ref "E11") (pin "9") (pinfunction "I8_9") (pintype "input"))
      (node (ref "U$3") (pin "AU2") (pinfunction "1_AU2") (pintype "bidirectional"))
    )
    (net (code "49") (name "Net-(E11A-I11)") (class "Default")
      (node (ref "E11") (pin "5") (pinfunction "I11_5") (pintype "input"))
      (node (ref "U$3") (pin "AU1") (pinfunction "1_AU1") (pintype "bidirectional"))
    )
    (net (code "50") (name "Net-(E12A-1)") (class "Default")
      (node (ref "E12") (pin "11") (pinfunction "1_11") (pintype "output"))
      (node (ref "R27") (pin "1") (pinfunction "1_1") (pintype "passive"))
      (node (ref "R43") (pin "2") (pinfunction "2_2") (pintype "passive"))
      (node (ref "U$3") (pin "AL1") (pinfunction "1_AL1") (pintype "bidirectional"))
    )
    (net (code "51") (name "Net-(E12A-R)") (class "Default")
      (node (ref "E12") (pin "9") (pinfunction "R_9") (pintype "input"))
      (node (ref "E8") (pin "3") (pinfunction "I1_3") (pintype "input"))
      (node (ref "E8") (pin "4") (pinfunction "O_4") (pintype "output"))
    )
    (net (code "52") (name "Net-(E12A-S)") (class "Default")
      (node (ref "E12") (pin "13") (pinfunction "S_13") (pintype "input"))
      (node (ref "E8") (pin "1") (pinfunction "O_1") (pintype "output"))
    )
    (net (code "53") (name "Net-(E13A-1)") (class "Default")
      (node (ref "E13") (pin "11") (pinfunction "1_11") (pintype "output"))
      (node (ref "R31") (pin "1") (pinfunction "1_1") (pintype "passive"))
      (node (ref "R47") (pin "2") (pinfunction "2_2") (pintype "passive"))
      (node (ref "U$3") (pin "AM1") (pinfunction "1_AM1") (pintype "bidirectional"))
    )
    (net (code "54") (name "Net-(E13A-R)") (class "Default")
      (node (ref "E13") (pin "9") (pinfunction "R_9") (pintype "input"))
      (node (ref "E8") (pin "10") (pinfunction "O_10") (pintype "output"))
      (node (ref "E8") (pin "11") (pinfunction "I0_11") (pintype "input"))
    )
    (net (code "55") (name "Net-(E13A-S)") (class "Default")
      (node (ref "E13") (pin "13") (pinfunction "S_13") (pintype "input"))
      (node (ref "E8") (pin "13") (pinfunction "O_13") (pintype "output"))
    )
    (net (code "56") (name "Net-(E14A-1)") (class "Default")
      (node (ref "E14") (pin "11") (pinfunction "1_11") (pintype "output"))
      (node (ref "R32") (pin "1") (pinfunction "1_1") (pintype "passive"))
      (node (ref "R48") (pin "2") (pinfunction "2_2") (pintype "passive"))
      (node (ref "U$3") (pin "AK1") (pinfunction "1_AK1") (pintype "bidirectional"))
    )
    (net (code "57") (name "Net-(E14A-R)") (class "Default")
      (node (ref "E14") (pin "9") (pinfunction "R_9") (pintype "input"))
      (node (ref "E9") (pin "10") (pinfunction "O_10") (pintype "output"))
      (node (ref "E9") (pin "11") (pinfunction "I0_11") (pintype "input"))
    )
    (net (code "58") (name "Net-(E14A-S)") (class "Default")
      (node (ref "E14") (pin "13") (pinfunction "S_13") (pintype "input"))
      (node (ref "E9") (pin "13") (pinfunction "O_13") (pintype "output"))
    )
    (net (code "59") (name "Net-(E15A-1)") (class "Default")
      (node (ref "E15") (pin "11") (pinfunction "1_11") (pintype "output"))
      (node (ref "R28") (pin "1") (pinfunction "1_1") (pintype "passive"))
      (node (ref "R44") (pin "2") (pinfunction "2_2") (pintype "passive"))
      (node (ref "U$3") (pin "AJ1") (pinfunction "1_AJ1") (pintype "bidirectional"))
    )
    (net (code "60") (name "Net-(E15A-R)") (class "Default")
      (node (ref "E15") (pin "9") (pinfunction "R_9") (pintype "input"))
      (node (ref "E9") (pin "3") (pinfunction "I1_3") (pintype "input"))
      (node (ref "E9") (pin "4") (pinfunction "O_4") (pintype "output"))
    )
    (net (code "61") (name "Net-(E15A-S)") (class "Default")
      (node (ref "E15") (pin "13") (pinfunction "S_13") (pintype "input"))
      (node (ref "E9") (pin "1") (pinfunction "O_1") (pintype "output"))
    )
    (net (code "62") (name "Net-(E16A-I0)") (class "Default")
      (node (ref "E16") (pin "1") (pinfunction "I0_1") (pintype "input"))
      (node (ref "E16") (pin "2") (pinfunction "I1_2") (pintype "input"))
      (node (ref "E21") (pin "12") (pinfunction "I1_12") (pintype "input"))
      (node (ref "E21") (pin "6") (pinfunction "I1_6") (pintype "input"))
      (node (ref "E22") (pin "8") (pinfunction "O_8") (pintype "output"))
    )
    (net (code "63") (name "Net-(E16A-O)") (class "Default")
      (node (ref "E16") (pin "3") (pinfunction "O_3") (pintype "output"))
      (node (ref "E21") (pin "2") (pinfunction "I0_2") (pintype "input"))
      (node (ref "E21") (pin "8") (pinfunction "I0_8") (pintype "input"))
    )
    (net (code "64") (name "Net-(E16B-I0)") (class "Default")
      (node (ref "E16") (pin "4") (pinfunction "I0_4") (pintype "input"))
      (node (ref "E16") (pin "5") (pinfunction "I1_5") (pintype "input"))
      (node (ref "E18") (pin "8") (pinfunction "O_8") (pintype "output"))
      (node (ref "E21") (pin "11") (pinfunction "I0_11") (pintype "input"))
      (node (ref "E21") (pin "9") (pinfunction "I1_9") (pintype "input"))
    )
    (net (code "65") (name "Net-(E16B-O)") (class "Default")
      (node (ref "E16") (pin "6") (pinfunction "O_6") (pintype "output"))
      (node (ref "E21") (pin "3") (pinfunction "I1_3") (pintype "input"))
      (node (ref "E21") (pin "5") (pinfunction "I0_5") (pintype "input"))
    )
    (net (code "66") (name "Net-(E17C-I0)") (class "Default")
      (node (ref "E17") (pin "1") (pinfunction "I0_1") (pintype "input"))
      (node (ref "E17") (pin "2") (pinfunction "I1_2") (pintype "input"))
      (node (ref "E17") (pin "4") (pinfunction "I2_4") (pintype "input"))
      (node (ref "E17") (pin "5") (pinfunction "I3_5") (pintype "input"))
      (node (ref "U$3") (pin "BK1") (pinfunction "1_BK1") (pintype "bidirectional"))
    )
    (net (code "67") (name "Net-(E17C-O)") (class "Default")
      (node (ref "E17") (pin "6") (pinfunction "O_6") (pintype "output"))
      (node (ref "E19") (pin "12") (pinfunction "I1_12") (pintype "input"))
      (node (ref "E19") (pin "2") (pinfunction "I0_2") (pintype "input"))
      (node (ref "E19") (pin "5") (pinfunction "I0_5") (pintype "input"))
      (node (ref "E19") (pin "9") (pinfunction "I1_9") (pintype "input"))
      (node (ref "E20") (pin "12") (pinfunction "I1_12") (pintype "input"))
      (node (ref "E20") (pin "2") (pinfunction "I0_2") (pintype "input"))
      (node (ref "E20") (pin "5") (pinfunction "I0_5") (pintype "input"))
      (node (ref "E20") (pin "8") (pinfunction "I0_8") (pintype "input"))
      (node (ref "E27") (pin "12") (pinfunction "I1_12") (pintype "input"))
      (node (ref "E27") (pin "2") (pinfunction "I0_2") (pintype "input"))
      (node (ref "E27") (pin "5") (pinfunction "I0_5") (pintype "input"))
      (node (ref "E27") (pin "9") (pinfunction "I1_9") (pintype "input"))
      (node (ref "E28") (pin "12") (pinfunction "I1_12") (pintype "input"))
      (node (ref "E28") (pin "2") (pinfunction "I0_2") (pintype "input"))
      (node (ref "E28") (pin "5") (pinfunction "I0_5") (pintype "input"))
      (node (ref "E28") (pin "8") (pinfunction "I0_8") (pintype "input"))
    )
    (net (code "68") (name "Net-(E17D-I0)") (class "Default")
      (node (ref "E17") (pin "10") (pinfunction "I1_10") (pintype "input"))
      (node (ref "E17") (pin "12") (pinfunction "I2_12") (pintype "input"))
      (node (ref "E17") (pin "13") (pinfunction "I3_13") (pintype "input"))
      (node (ref "E17") (pin "9") (pinfunction "I0_9") (pintype "input"))
      (node (ref "U$3") (pin "AM2") (pinfunction "1_AM2") (pintype "bidirectional"))
    )
    (net (code "69") (name "Net-(E17D-O)") (class "Default")
      (node (ref "E1") (pin "12") (pinfunction "I1_12") (pintype "input"))
      (node (ref "E1") (pin "2") (pinfunction "I0_2") (pintype "input"))
      (node (ref "E1") (pin "5") (pinfunction "I0_5") (pintype "input"))
      (node (ref "E1") (pin "9") (pinfunction "I1_9") (pintype "input"))
      (node (ref "E17") (pin "8") (pinfunction "O_8") (pintype "output"))
      (node (ref "E2") (pin "12") (pinfunction "I1_12") (pintype "input"))
      (node (ref "E2") (pin "2") (pinfunction "I0_2") (pintype "input"))
      (node (ref "E2") (pin "5") (pinfunction "I0_5") (pintype "input"))
      (node (ref "E2") (pin "8") (pinfunction "I0_8") (pintype "input"))
      (node (ref "E8") (pin "12") (pinfunction "I1_12") (pintype "input"))
      (node (ref "E8") (pin "2") (pinfunction "I0_2") (pintype "input"))
      (node (ref "E8") (pin "5") (pinfunction "I0_5") (pintype "input"))
      (node (ref "E8") (pin "9") (pinfunction "I1_9") (pintype "input"))
      (node (ref "E9") (pin "12") (pinfunction "I1_12") (pintype "input"))
      (node (ref "E9") (pin "2") (pinfunction "I0_2") (pintype "input"))
      (node (ref "E9") (pin "5") (pinfunction "I0_5") (pintype "input"))
      (node (ref "E9") (pin "8") (pinfunction "I0_8") (pintype "input"))
    )
    (net (code "70") (name "Net-(E18A-I4)") (class "Default")
      (node (ref "E18") (pin "1") (pinfunction "I4_1") (pintype "input"))
      (node (ref "U$3") (pin "BD1") (pinfunction "1_BD1") (pintype "bidirectional"))
    )
    (net (code "71") (name "Net-(E18A-I6)") (class "Default")
      (node (ref "E18") (pin "3") (pinfunction "I6_3") (pintype "input"))
      (node (ref "U$3") (pin "BD2") (pinfunction "1_BD2") (pintype "bidirectional"))
    )
    (net (code "72") (name "Net-(E18A-I8)") (class "Default")
      (node (ref "E18") (pin "9") (pinfunction "I8_9") (pintype "input"))
      (node (ref "U$3") (pin "BA1") (pinfunction "1_BA1") (pintype "bidirectional"))
    )
    (net (code "73") (name "Net-(E18A-I11)") (class "Default")
      (node (ref "E18") (pin "5") (pinfunction "I11_5") (pintype "input"))
      (node (ref "U$3") (pin "BC1") (pinfunction "1_BC1") (pintype "bidirectional"))
    )
    (net (code "74") (name "Net-(E19A-I1)") (class "Default")
      (node (ref "E19") (pin "3") (pinfunction "I1_3") (pintype "input"))
      (node (ref "E19") (pin "4") (pinfunction "O_4") (pintype "output"))
      (node (ref "E23") (pin "9") (pinfunction "R_9") (pintype "input"))
    )
    (net (code "75") (name "Net-(E19A-O)") (class "Default")
      (node (ref "E19") (pin "1") (pinfunction "O_1") (pintype "output"))
      (node (ref "E23") (pin "13") (pinfunction "S_13") (pintype "input"))
    )
    (net (code "76") (name "Net-(E19B-I1)") (class "Default")
      (node (ref "E19") (pin "6") (pinfunction "I1_6") (pintype "input"))
      (node (ref "U$3") (pin "BR2") (pinfunction "1_BR2") (pintype "bidirectional"))
    )
    (net (code "77") (name "Net-(E19C-I0)") (class "Default")
      (node (ref "E19") (pin "8") (pinfunction "I0_8") (pintype "input"))
      (node (ref "U$3") (pin "BP2") (pinfunction "1_BP2") (pintype "bidirectional"))
    )
    (net (code "78") (name "Net-(E19C-O)") (class "Default")
      (node (ref "E19") (pin "10") (pinfunction "O_10") (pintype "output"))
      (node (ref "E19") (pin "11") (pinfunction "I0_11") (pintype "input"))
      (node (ref "E24") (pin "9") (pinfunction "R_9") (pintype "input"))
    )
    (net (code "79") (name "Net-(E19D-O)") (class "Default")
      (node (ref "E19") (pin "13") (pinfunction "O_13") (pintype "output"))
      (node (ref "E24") (pin "13") (pinfunction "S_13") (pintype "input"))
    )
    (net (code "80") (name "Net-(E20A-I1)") (class "Default")
      (node (ref "E20") (pin "3") (pinfunction "I1_3") (pintype "input"))
      (node (ref "E20") (pin "4") (pinfunction "O_4") (pintype "output"))
      (node (ref "E26") (pin "9") (pinfunction "R_9") (pintype "input"))
    )
    (net (code "81") (name "Net-(E20A-O)") (class "Default")
      (node (ref "E20") (pin "1") (pinfunction "O_1") (pintype "output"))
      (node (ref "E26") (pin "13") (pinfunction "S_13") (pintype "input"))
    )
    (net (code "82") (name "Net-(E20B-I1)") (class "Default")
      (node (ref "E20") (pin "6") (pinfunction "I1_6") (pintype "input"))
      (node (ref "U$3") (pin "BL1") (pinfunction "1_BL1") (pintype "bidirectional"))
    )
    (net (code "83") (name "Net-(E20C-I1)") (class "Default")
      (node (ref "E20") (pin "9") (pinfunction "I1_9") (pintype "input"))
      (node (ref "U$3") (pin "BN2") (pinfunction "1_BN2") (pintype "bidirectional"))
    )
    (net (code "84") (name "Net-(E20C-O)") (class "Default")
      (node (ref "E20") (pin "10") (pinfunction "O_10") (pintype "output"))
      (node (ref "E20") (pin "11") (pinfunction "I0_11") (pintype "input"))
      (node (ref "E25") (pin "9") (pinfunction "R_9") (pintype "input"))
    )
    (net (code "85") (name "Net-(E20D-O)") (class "Default")
      (node (ref "E20") (pin "13") (pinfunction "O_13") (pintype "output"))
      (node (ref "E25") (pin "13") (pinfunction "S_13") (pintype "input"))
    )
    (net (code "86") (name "Net-(E21A-O)") (class "Default")
      (node (ref "E21") (pin "1") (pinfunction "O_1") (pintype "open_collector"))
      (node (ref "Q5") (pin "2") (pinfunction "B_2") (pintype "passive"))
      (node (ref "R13") (pin "1") (pinfunction "1_1") (pintype "passive"))
    )
    (net (code "87") (name "Net-(E21B-O)") (class "Default")
      (node (ref "E21") (pin "4") (pinfunction "O_4") (pintype "open_collector"))
      (node (ref "Q6") (pin "2") (pinfunction "B_2") (pintype "passive"))
      (node (ref "R16") (pin "1") (pinfunction "1_1") (pintype "passive"))
    )
    (net (code "88") (name "Net-(E21C-O)") (class "Default")
      (node (ref "E21") (pin "10") (pinfunction "O_10") (pintype "open_collector"))
      (node (ref "Q7") (pin "2") (pinfunction "B_2") (pintype "passive"))
      (node (ref "R19") (pin "1") (pinfunction "1_1") (pintype "passive"))
    )
    (net (code "89") (name "Net-(E21D-O)") (class "Default")
      (node (ref "E21") (pin "13") (pinfunction "O_13") (pintype "open_collector"))
      (node (ref "Q8") (pin "2") (pinfunction "B_2") (pintype "passive"))
      (node (ref "R22") (pin "1") (pinfunction "1_1") (pintype "passive"))
    )
    (net (code "90") (name "Net-(E22A-I4)") (class "Default")
      (node (ref "E22") (pin "1") (pinfunction "I4_1") (pintype "input"))
      (node (ref "U$3") (pin "BF2") (pinfunction "1_BF2") (pintype "bidirectional"))
    )
    (net (code "91") (name "Net-(E22A-I6)") (class "Default")
      (node (ref "E22") (pin "3") (pinfunction "I6_3") (pintype "input"))
      (node (ref "U$3") (pin "BH1") (pinfunction "1_BH1") (pintype "bidirectional"))
    )
    (net (code "92") (name "Net-(E22A-I8)") (class "Default")
      (node (ref "E22") (pin "9") (pinfunction "I8_9") (pintype "input"))
      (node (ref "U$3") (pin "BF1") (pinfunction "1_BF1") (pintype "bidirectional"))
    )
    (net (code "93") (name "Net-(E22A-I11)") (class "Default")
      (node (ref "E22") (pin "5") (pinfunction "I11_5") (pintype "input"))
      (node (ref "U$3") (pin "BE2") (pinfunction "1_BE2") (pintype "bidirectional"))
    )
    (net (code "94") (name "Net-(E23A-1)") (class "Default")
      (node (ref "E23") (pin "11") (pinfunction "1_11") (pintype "output"))
      (node (ref "R33") (pin "1") (pinfunction "1_1") (pintype "passive"))
      (node (ref "R49") (pin "2") (pinfunction "2_2") (pintype "passive"))
      (node (ref "U$3") (pin "BM2") (pinfunction "1_BM2") (pintype "bidirectional"))
    )
    (net (code "95") (name "Net-(E24A-1)") (class "Default")
      (node (ref "E24") (pin "11") (pinfunction "1_11") (pintype "output"))
      (node (ref "R37") (pin "1") (pinfunction "1_1") (pintype "passive"))
      (node (ref "R53") (pin "2") (pinfunction "2_2") (pintype "passive"))
      (node (ref "U$3") (pin "BT2") (pinfunction "1_BT2") (pintype "bidirectional"))
    )
    (net (code "96") (name "Net-(E25A-1)") (class "Default")
      (node (ref "E25") (pin "11") (pinfunction "1_11") (pintype "output"))
      (node (ref "R38") (pin "1") (pinfunction "1_1") (pintype "passive"))
      (node (ref "R54") (pin "2") (pinfunction "2_2") (pintype "passive"))
      (node (ref "U$3") (pin "BN1") (pinfunction "1_BN1") (pintype "bidirectional"))
    )
    (net (code "97") (name "Net-(E26A-1)") (class "Default")
      (node (ref "E26") (pin "11") (pinfunction "1_11") (pintype "output"))
      (node (ref "R34") (pin "1") (pinfunction "1_1") (pintype "passive"))
      (node (ref "R50") (pin "2") (pinfunction "2_2") (pintype "passive"))
      (node (ref "U$3") (pin "BM1") (pinfunction "1_BM1") (pintype "bidirectional"))
    )
    (net (code "98") (name "Net-(E27A-I1)") (class "Default")
      (node (ref "E27") (pin "3") (pinfunction "I1_3") (pintype "input"))
      (node (ref "E27") (pin "4") (pinfunction "O_4") (pintype "output"))
      (node (ref "E29") (pin "9") (pinfunction "R_9") (pintype "input"))
    )
    (net (code "99") (name "Net-(E27A-O)") (class "Default")
      (node (ref "E27") (pin "1") (pinfunction "O_1") (pintype "output"))
      (node (ref "E29") (pin "13") (pinfunction "S_13") (pintype "input"))
    )
    (net (code "100") (name "Net-(E27B-I1)") (class "Default")
      (node (ref "E27") (pin "6") (pinfunction "I1_6") (pintype "input"))
      (node (ref "U$3") (pin "BV2") (pinfunction "1_BV2") (pintype "bidirectional"))
    )
    (net (code "101") (name "Net-(E27C-I0)") (class "Default")
      (node (ref "E27") (pin "8") (pinfunction "I0_8") (pintype "input"))
      (node (ref "U$3") (pin "BU2") (pinfunction "1_BU2") (pintype "bidirectional"))
    )
    (net (code "102") (name "Net-(E27C-O)") (class "Default")
      (node (ref "E27") (pin "10") (pinfunction "O_10") (pintype "output"))
      (node (ref "E27") (pin "11") (pinfunction "I0_11") (pintype "input"))
      (node (ref "E30") (pin "9") (pinfunction "R_9") (pintype "input"))
    )
    (net (code "103") (name "Net-(E27D-O)") (class "Default")
      (node (ref "E27") (pin "13") (pinfunction "O_13") (pintype "output"))
      (node (ref "E30") (pin "13") (pinfunction "S_13") (pintype "input"))
    )
    (net (code "104") (name "Net-(E28A-I1)") (class "Default")
      (node (ref "E28") (pin "3") (pinfunction "I1_3") (pintype "input"))
      (node (ref "E28") (pin "4") (pinfunction "O_4") (pintype "output"))
      (node (ref "E32") (pin "9") (pinfunction "R_9") (pintype "input"))
    )
    (net (code "105") (name "Net-(E28A-O)") (class "Default")
      (node (ref "E28") (pin "1") (pinfunction "O_1") (pintype "output"))
      (node (ref "E32") (pin "13") (pinfunction "S_13") (pintype "input"))
    )
    (net (code "106") (name "Net-(E28B-I1)") (class "Default")
      (node (ref "E28") (pin "6") (pinfunction "I1_6") (pintype "input"))
      (node (ref "U$3") (pin "BP1") (pinfunction "1_BP1") (pintype "bidirectional"))
    )
    (net (code "107") (name "Net-(E28C-I1)") (class "Default")
      (node (ref "E28") (pin "9") (pinfunction "I1_9") (pintype "input"))
      (node (ref "U$3") (pin "BS2") (pinfunction "1_BS2") (pintype "bidirectional"))
    )
    (net (code "108") (name "Net-(E28C-O)") (class "Default")
      (node (ref "E28") (pin "10") (pinfunction "O_10") (pintype "output"))
      (node (ref "E28") (pin "11") (pinfunction "I0_11") (pintype "input"))
      (node (ref "E31") (pin "9") (pinfunction "R_9") (pintype "input"))
    )
    (net (code "109") (name "Net-(E28D-O)") (class "Default")
      (node (ref "E28") (pin "13") (pinfunction "O_13") (pintype "output"))
      (node (ref "E31") (pin "13") (pinfunction "S_13") (pintype "input"))
    )
    (net (code "110") (name "Net-(E29A-1)") (class "Default")
      (node (ref "E29") (pin "11") (pinfunction "1_11") (pintype "output"))
      (node (ref "R35") (pin "1") (pinfunction "1_1") (pintype "passive"))
      (node (ref "R51") (pin "2") (pinfunction "2_2") (pintype "passive"))
      (node (ref "U$3") (pin "BU1") (pinfunction "1_BU1") (pintype "bidirectional"))
    )
    (net (code "111") (name "Net-(E30A-1)") (class "Default")
      (node (ref "E30") (pin "11") (pinfunction "1_11") (pintype "output"))
      (node (ref "R39") (pin "1") (pinfunction "1_1") (pintype "passive"))
      (node (ref "R55") (pin "2") (pinfunction "2_2") (pintype "passive"))
      (node (ref "U$3") (pin "BV1") (pinfunction "1_BV1") (pintype "bidirectional"))
    )
    (net (code "112") (name "Net-(E31A-1)") (class "Default")
      (node (ref "E31") (pin "11") (pinfunction "1_11") (pintype "output"))
      (node (ref "R40") (pin "1") (pinfunction "1_1") (pintype "passive"))
      (node (ref "R56") (pin "2") (pinfunction "2_2") (pintype "passive"))
      (node (ref "U$3") (pin "BS1") (pinfunction "1_BS1") (pintype "bidirectional"))
    )
    (net (code "113") (name "Net-(E32A-1)") (class "Default")
      (node (ref "E32") (pin "11") (pinfunction "1_11") (pintype "output"))
      (node (ref "R36") (pin "1") (pinfunction "1_1") (pintype "passive"))
      (node (ref "R52") (pin "2") (pinfunction "2_2") (pintype "passive"))
      (node (ref "U$3") (pin "BR1") (pinfunction "1_BR1") (pintype "bidirectional"))
    )
    (net (code "114") (name "VCC") (class "Default")
      (node (ref "C1") (pin "1") (pinfunction "1_1") (pintype "passive"))
      (node (ref "C10") (pin "1") (pinfunction "1_1") (pintype "passive"))
      (node (ref "C11") (pin "1") (pinfunction "1_1") (pintype "passive"))
      (node (ref "C12") (pin "1") (pinfunction "1_1") (pintype "passive"))
      (node (ref "C13") (pin "1") (pinfunction "1_1") (pintype "passive"))
      (node (ref "C14") (pin "1") (pinfunction "1_1") (pintype "passive"))
      (node (ref "C15") (pin "1") (pinfunction "1_1") (pintype "passive"))
      (node (ref "C16") (pin "1") (pinfunction "1_1") (pintype "passive"))
      (node (ref "C17") (pin "1") (pinfunction "1_1") (pintype "passive"))
      (node (ref "C18") (pin "1") (pinfunction "1_1") (pintype "passive"))
      (node (ref "C19") (pin "1") (pinfunction "1_1") (pintype "passive"))
      (node (ref "C2") (pin "1") (pinfunction "1_1") (pintype "passive"))
      (node (ref "C20") (pin "1") (pinfunction "1_1") (pintype "passive"))
      (node (ref "C21") (pin "1") (pinfunction "1_1") (pintype "passive"))
      (node (ref "C22") (pin "1") (pinfunction "1_1") (pintype "passive"))
      (node (ref "C23") (pin "1") (pinfunction "1_1") (pintype "passive"))
      (node (ref "C24") (pin "1") (pinfunction "1_1") (pintype "passive"))
      (node (ref "C25") (pin "1") (pinfunction "1_1") (pintype "passive"))
      (node (ref "C26") (pin "1") (pinfunction "1_1") (pintype "passive"))
      (node (ref "C27") (pin "1") (pinfunction "1_1") (pintype "passive"))
      (node (ref "C28") (pin "1") (pinfunction "1_1") (pintype "passive"))
      (node (ref "C29") (pin "1") (pinfunction "1_1") (pintype "passive"))
      (node (ref "C3") (pin "1") (pinfunction "1_1") (pintype "passive"))
      (node (ref "C30") (pin "1") (pinfunction "1_1") (pintype "passive"))
      (node (ref "C31") (pin "1") (pinfunction "1_1") (pintype "passive"))
      (node (ref "C32") (pin "1") (pinfunction "1_1") (pintype "passive"))
      (node (ref "C33") (pin "1") (pinfunction "1_1") (pintype "passive"))
      (node (ref "C34") (pin "1") (pinfunction "1_1") (pintype "passive"))
      (node (ref "C35") (pin "1") (pinfunction "1_1") (pintype "passive"))
      (node (ref "C36") (pin "1") (pinfunction "1_1") (pintype "passive"))
      (node (ref "C37") (pin "1") (pinfunction "1_1") (pintype "passive"))
      (node (ref "C38") (pin "1") (pinfunction "1_1") (pintype "passive"))
      (node (ref "C39") (pin "1") (pinfunction "1_1") (pintype "passive"))
      (node (ref "C4") (pin "1") (pinfunction "1_1") (pintype "passive"))
      (node (ref "C40") (pin "1") (pinfunction "1_1") (pintype "passive"))
      (node (ref "C41") (pin "+") (pinfunction "+_+") (pintype "passive"))
      (node (ref "C42") (pin "+") (pinfunction "+_+") (pintype "passive"))
      (node (ref "C5") (pin "1") (pinfunction "1_1") (pintype "passive"))
      (node (ref "C6") (pin "1") (pinfunction "1_1") (pintype "passive"))
      (node (ref "C7") (pin "1") (pinfunction "1_1") (pintype "passive"))
      (node (ref "C8") (pin "1") (pinfunction "1_1") (pintype "passive"))
      (node (ref "C9") (pin "1") (pinfunction "1_1") (pintype "passive"))
      (node (ref "R1") (pin "2") (pinfunction "2_2") (pintype "passive"))
      (node (ref "R10") (pin "2") (pinfunction "2_2") (pintype "passive"))
      (node (ref "R11") (pin "2") (pinfunction "2_2") (pintype "passive"))
      (node (ref "R13") (pin "2") (pinfunction "2_2") (pintype "passive"))
      (node (ref "R14") (pin "2") (pinfunction "2_2") (pintype "passive"))
      (node (ref "R16") (pin "2") (pinfunction "2_2") (pintype "passive"))
      (node (ref "R17") (pin "2") (pinfunction "2_2") (pintype "passive"))
      (node (ref "R19") (pin "2") (pinfunction "2_2") (pintype "passive"))
      (node (ref "R2") (pin "2") (pinfunction "2_2") (pintype "passive"))
      (node (ref "R20") (pin "2") (pinfunction "2_2") (pintype "passive"))
      (node (ref "R22") (pin "2") (pinfunction "2_2") (pintype "passive"))
      (node (ref "R23") (pin "2") (pinfunction "2_2") (pintype "passive"))
      (node (ref "R25") (pin "2") (pinfunction "2_2") (pintype "passive"))
      (node (ref "R26") (pin "2") (pinfunction "2_2") (pintype "passive"))
      (node (ref "R27") (pin "2") (pinfunction "2_2") (pintype "passive"))
      (node (ref "R28") (pin "2") (pinfunction "2_2") (pintype "passive"))
      (node (ref "R29") (pin "2") (pinfunction "2_2") (pintype "passive"))
      (node (ref "R30") (pin "2") (pinfunction "2_2") (pintype "passive"))
      (node (ref "R31") (pin "2") (pinfunction "2_2") (pintype "passive"))
      (node (ref "R32") (pin "2") (pinfunction "2_2") (pintype "passive"))
      (node (ref "R33") (pin "2") (pinfunction "2_2") (pintype "passive"))
      (node (ref "R34") (pin "2") (pinfunction "2_2") (pintype "passive"))
      (node (ref "R35") (pin "2") (pinfunction "2_2") (pintype "passive"))
      (node (ref "R36") (pin "2") (pinfunction "2_2") (pintype "passive"))
      (node (ref "R37") (pin "2") (pinfunction "2_2") (pintype "passive"))
      (node (ref "R38") (pin "2") (pinfunction "2_2") (pintype "passive"))
      (node (ref "R39") (pin "2") (pinfunction "2_2") (pintype "passive"))
      (node (ref "R4") (pin "2") (pinfunction "2_2") (pintype "passive"))
      (node (ref "R40") (pin "2") (pinfunction "2_2") (pintype "passive"))
      (node (ref "R5") (pin "2") (pinfunction "2_2") (pintype "passive"))
      (node (ref "R7") (pin "2") (pinfunction "2_2") (pintype "passive"))
      (node (ref "R8") (pin "2") (pinfunction "2_2") (pintype "passive"))
      (node (ref "U$3") (pin "AA2") (pinfunction "1_AA2") (pintype "bidirectional"))
      (node (ref "U$3") (pin "BA2") (pinfunction "1_BA2") (pintype "bidirectional"))
    )
    (net (code "115") (name "unconnected-(E3A-0-Pad12)") (class "Default")
      (node (ref "E3") (pin "12") (pinfunction "0_12") (pintype "output"))
    )
    (net (code "116") (name "unconnected-(E4A-0-Pad12)") (class "Default")
      (node (ref "E4") (pin "12") (pinfunction "0_12") (pintype "output"))
    )
    (net (code "117") (name "unconnected-(E5A-0-Pad12)") (class "Default")
      (node (ref "E5") (pin "12") (pinfunction "0_12") (pintype "output"))
    )
    (net (code "118") (name "unconnected-(E6A-0-Pad12)") (class "Default")
      (node (ref "E6") (pin "12") (pinfunction "0_12") (pintype "output"))
    )
    (net (code "119") (name "unconnected-(E7A-I2-Pad6)") (class "Default")
      (node (ref "E7") (pin "6") (pinfunction "I2_6") (pintype "input"))
    )
    (net (code "120") (name "unconnected-(E7A-I9-Pad12)") (class "Default")
      (node (ref "E7") (pin "12") (pinfunction "I9_12") (pintype "passive"))
    )
    (net (code "121") (name "unconnected-(E7A-I10-Pad11)") (class "Default")
      (node (ref "E7") (pin "11") (pinfunction "I10_11") (pintype "passive"))
    )
    (net (code "122") (name "unconnected-(E11A-I2-Pad6)") (class "Default")
      (node (ref "E11") (pin "6") (pinfunction "I2_6") (pintype "input"))
    )
    (net (code "123") (name "unconnected-(E11A-I9-Pad12)") (class "Default")
      (node (ref "E11") (pin "12") (pinfunction "I9_12") (pintype "passive"))
    )
    (net (code "124") (name "unconnected-(E11A-I10-Pad11)") (class "Default")
      (node (ref "E11") (pin "11") (pinfunction "I10_11") (pintype "passive"))
    )
    (net (code "125") (name "unconnected-(E12A-0-Pad12)") (class "Default")
      (node (ref "E12") (pin "12") (pinfunction "0_12") (pintype "output"))
    )
    (net (code "126") (name "unconnected-(E13A-0-Pad12)") (class "Default")
      (node (ref "E13") (pin "12") (pinfunction "0_12") (pintype "output"))
    )
    (net (code "127") (name "unconnected-(E14A-0-Pad12)") (class "Default")
      (node (ref "E14") (pin "12") (pinfunction "0_12") (pintype "output"))
    )
    (net (code "128") (name "unconnected-(E15A-0-Pad12)") (class "Default")
      (node (ref "E15") (pin "12") (pinfunction "0_12") (pintype "output"))
    )
    (net (code "129") (name "unconnected-(E18A-I2-Pad6)") (class "Default")
      (node (ref "E18") (pin "6") (pinfunction "I2_6") (pintype "input"))
    )
    (net (code "130") (name "unconnected-(E18A-I9-Pad12)") (class "Default")
      (node (ref "E18") (pin "12") (pinfunction "I9_12") (pintype "passive"))
    )
    (net (code "131") (name "unconnected-(E18A-I10-Pad11)") (class "Default")
      (node (ref "E18") (pin "11") (pinfunction "I10_11") (pintype "passive"))
    )
    (net (code "132") (name "unconnected-(E22A-I2-Pad6)") (class "Default")
      (node (ref "E22") (pin "6") (pinfunction "I2_6") (pintype "input"))
    )
    (net (code "133") (name "unconnected-(E22A-I9-Pad12)") (class "Default")
      (node (ref "E22") (pin "12") (pinfunction "I9_12") (pintype "passive"))
    )
    (net (code "134") (name "unconnected-(E22A-I10-Pad11)") (class "Default")
      (node (ref "E22") (pin "11") (pinfunction "I10_11") (pintype "passive"))
    )
    (net (code "135") (name "unconnected-(E23A-0-Pad12)") (class "Default")
      (node (ref "E23") (pin "12") (pinfunction "0_12") (pintype "output"))
    )
    (net (code "136") (name "unconnected-(E24A-0-Pad12)") (class "Default")
      (node (ref "E24") (pin "12") (pinfunction "0_12") (pintype "output"))
    )
    (net (code "137") (name "unconnected-(E25A-0-Pad12)") (class "Default")
      (node (ref "E25") (pin "12") (pinfunction "0_12") (pintype "output"))
    )
    (net (code "138") (name "unconnected-(E26A-0-Pad12)") (class "Default")
      (node (ref "E26") (pin "12") (pinfunction "0_12") (pintype "output"))
    )
    (net (code "139") (name "unconnected-(E29A-0-Pad12)") (class "Default")
      (node (ref "E29") (pin "12") (pinfunction "0_12") (pintype "output"))
    )
    (net (code "140") (name "unconnected-(E30A-0-Pad12)") (class "Default")
      (node (ref "E30") (pin "12") (pinfunction "0_12") (pintype "output"))
    )
    (net (code "141") (name "unconnected-(E31A-0-Pad12)") (class "Default")
      (node (ref "E31") (pin "12") (pinfunction "0_12") (pintype "output"))
    )
    (net (code "142") (name "unconnected-(E32A-0-Pad12)") (class "Default")
      (node (ref "E32") (pin "12") (pinfunction "0_12") (pintype "output"))
    )
  )
)
